# ProPrj_T113__2026-08-06.net
KiCad netlist of a schematic drawn in EasyEDA Pro
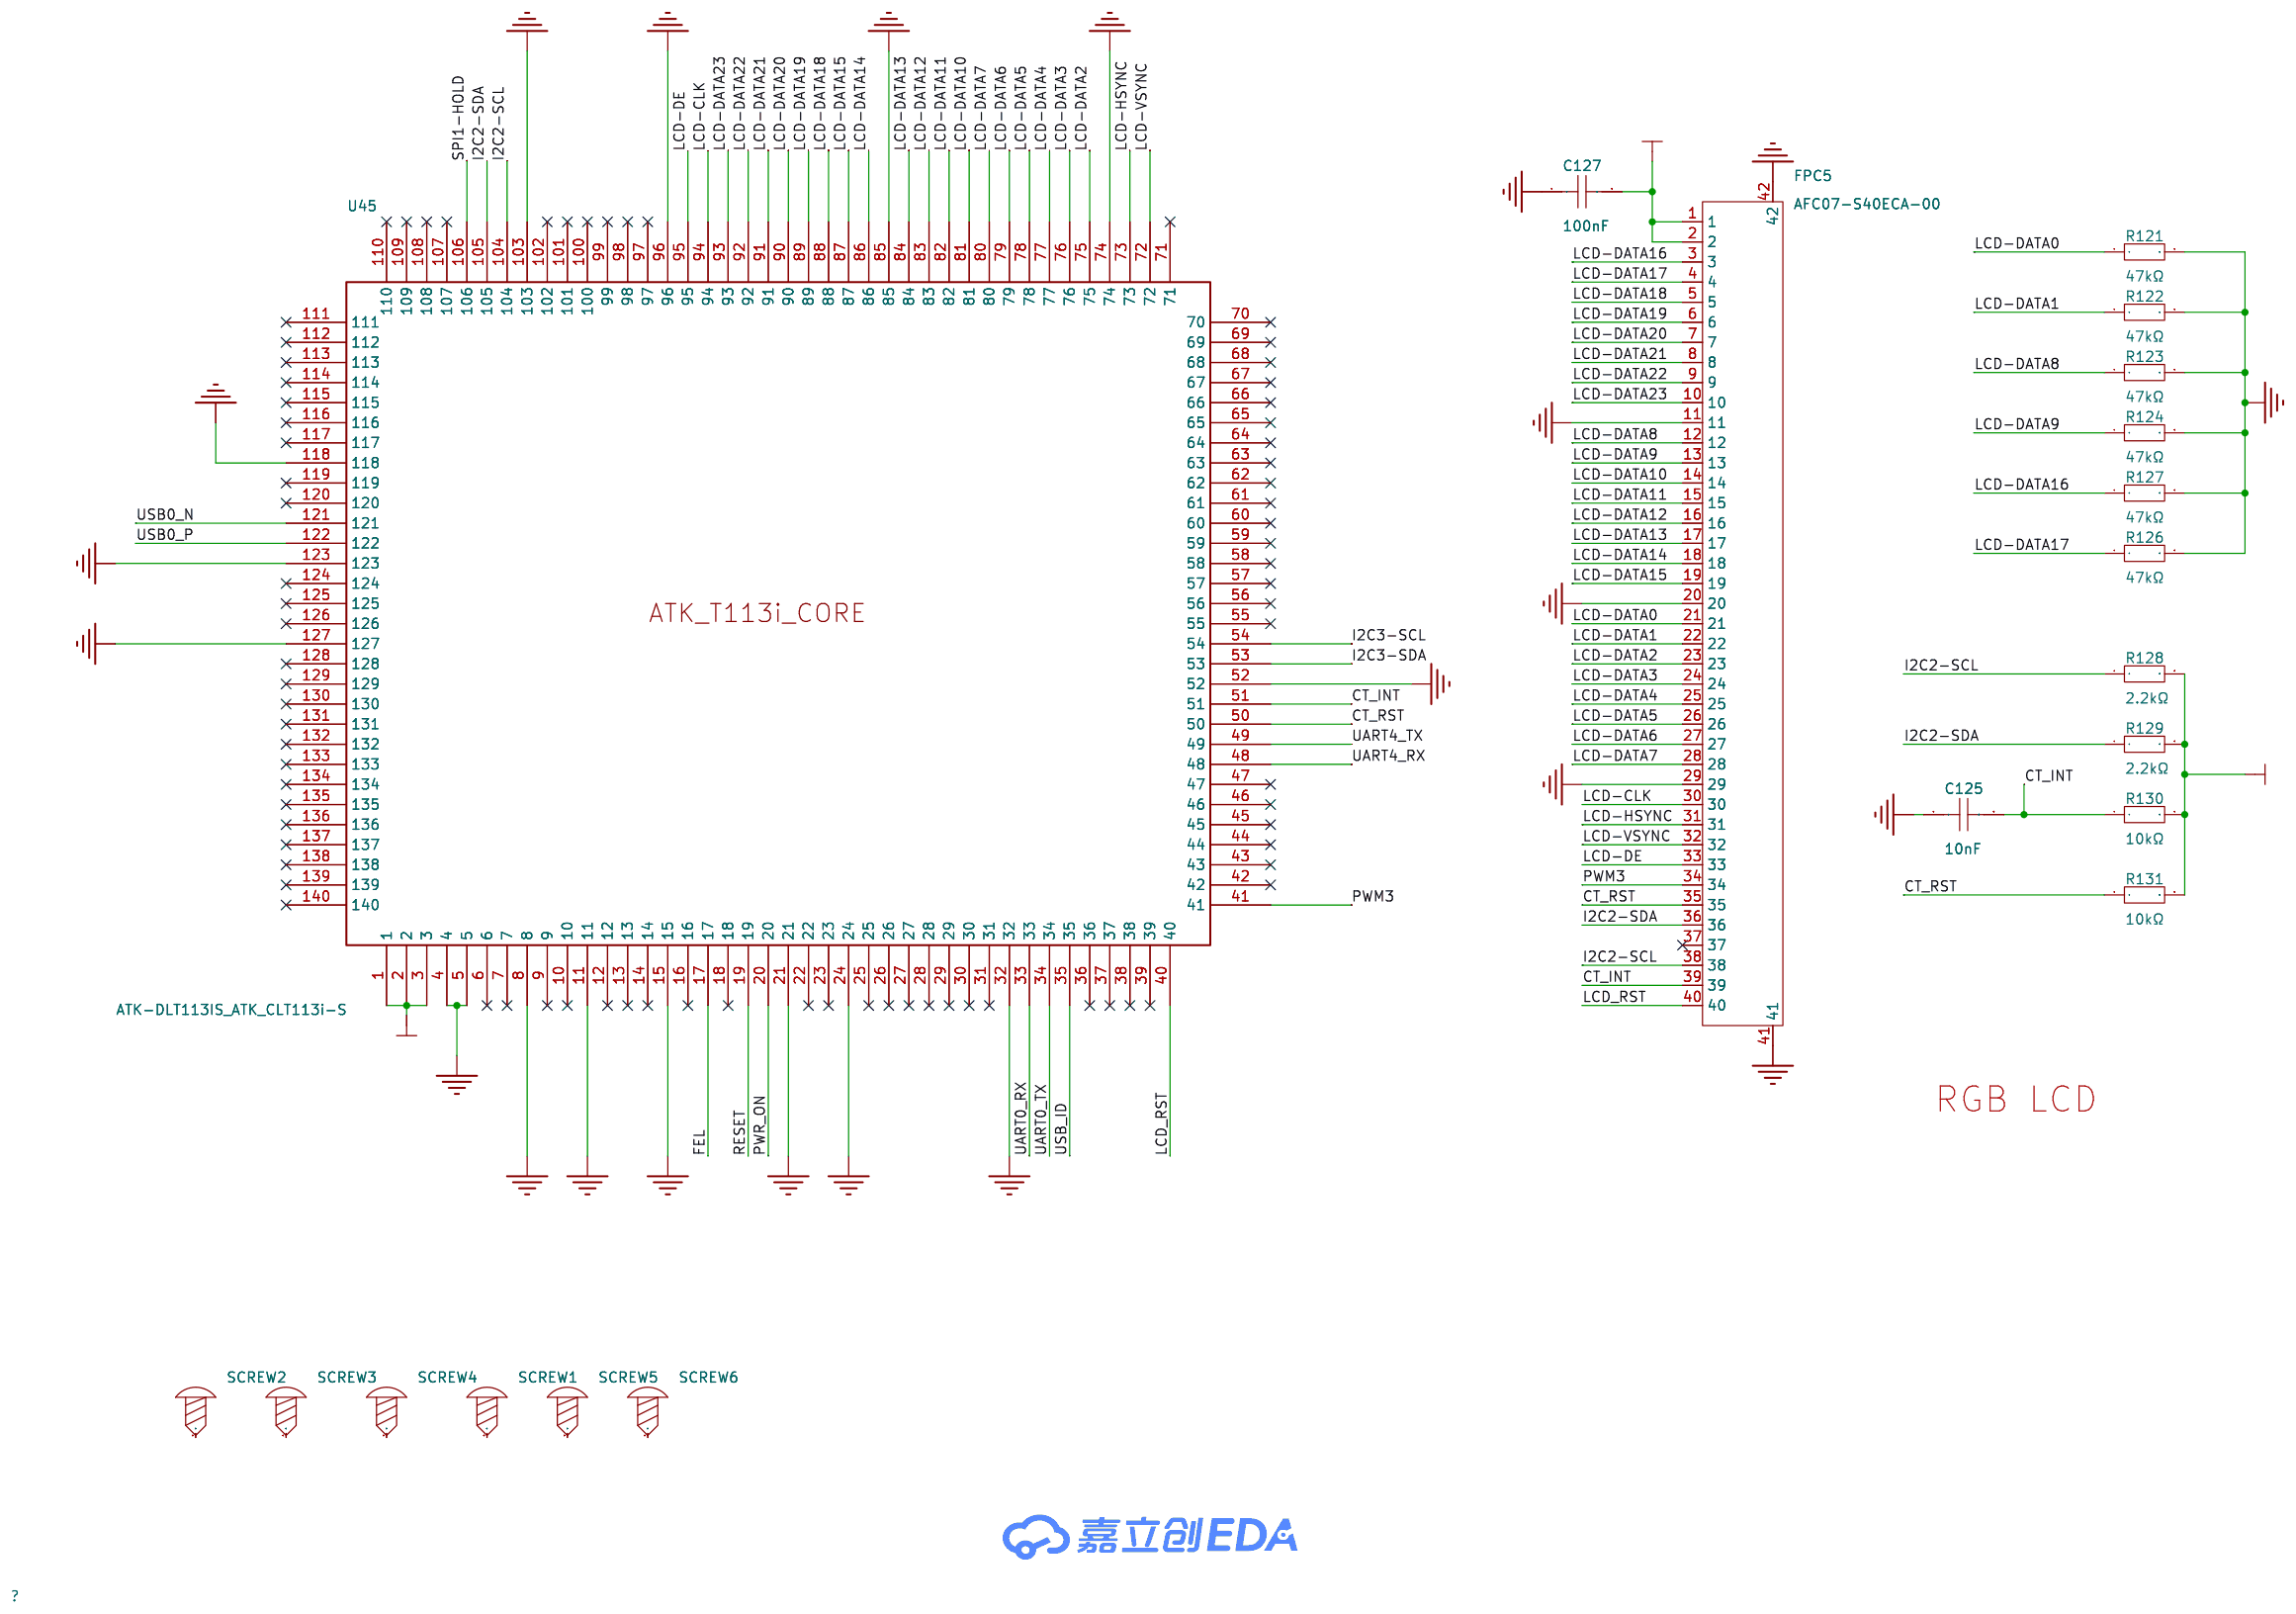
[diagram p0: P1]
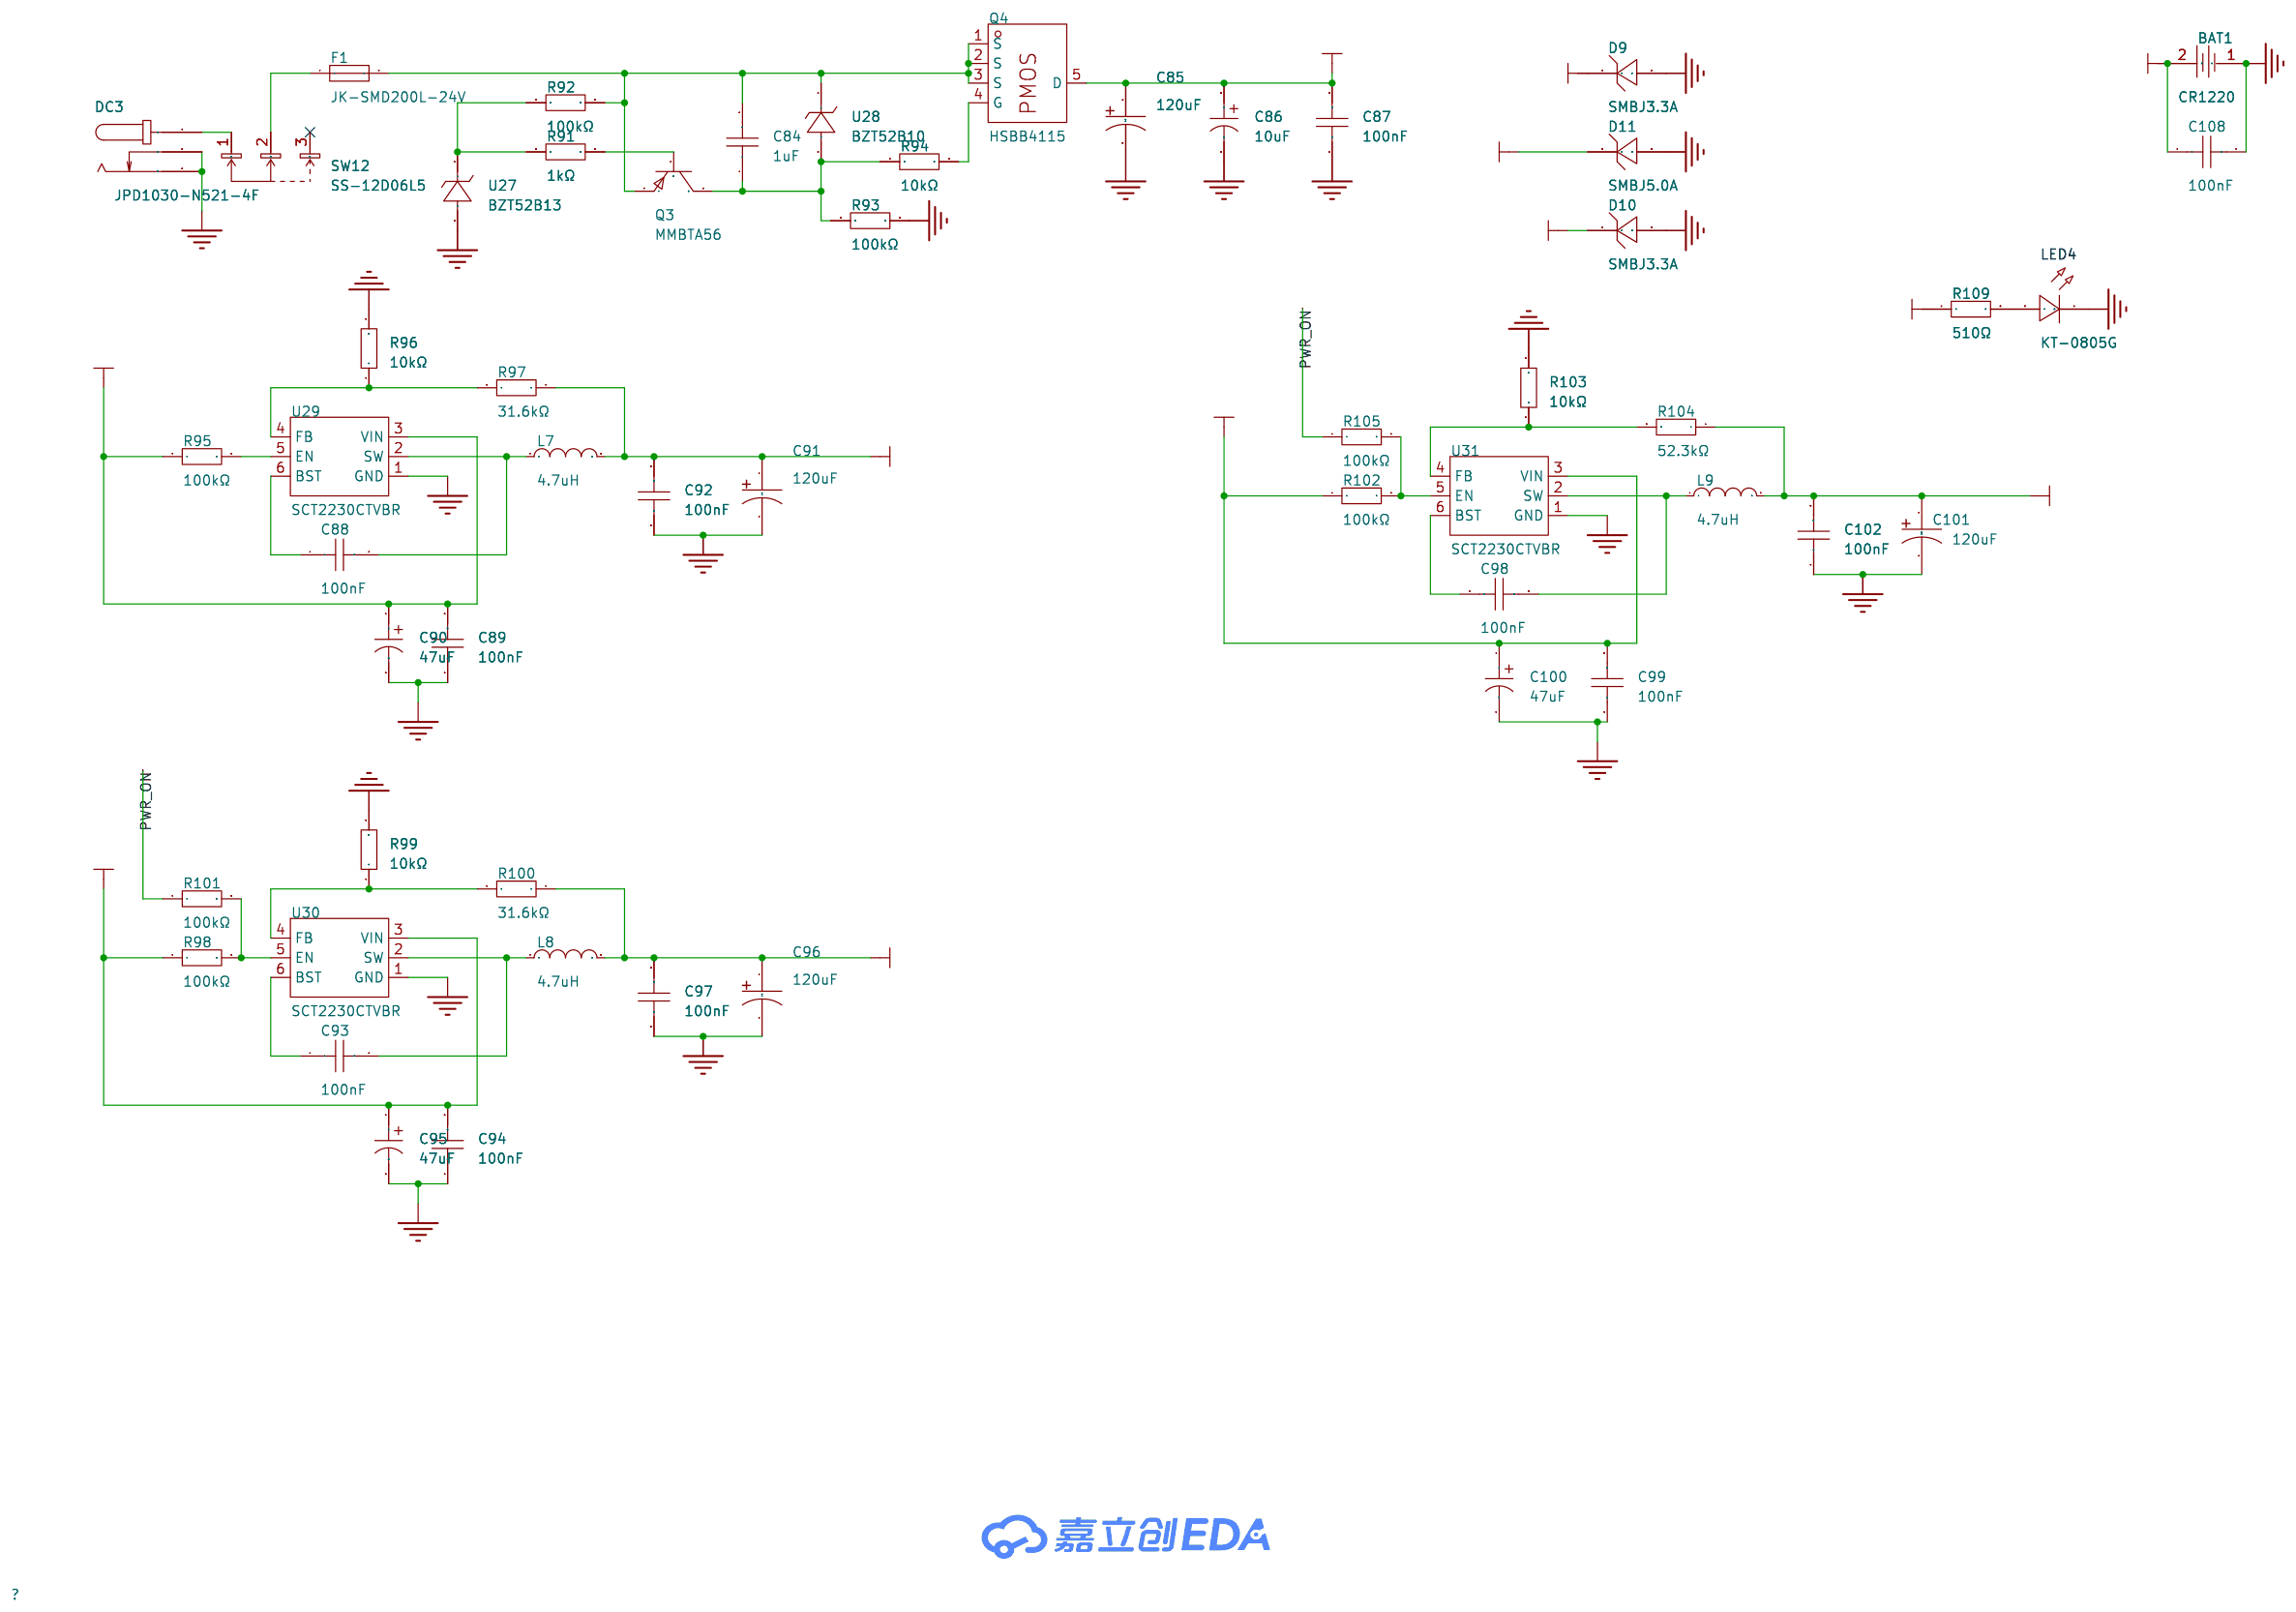
[diagram p1: P4]
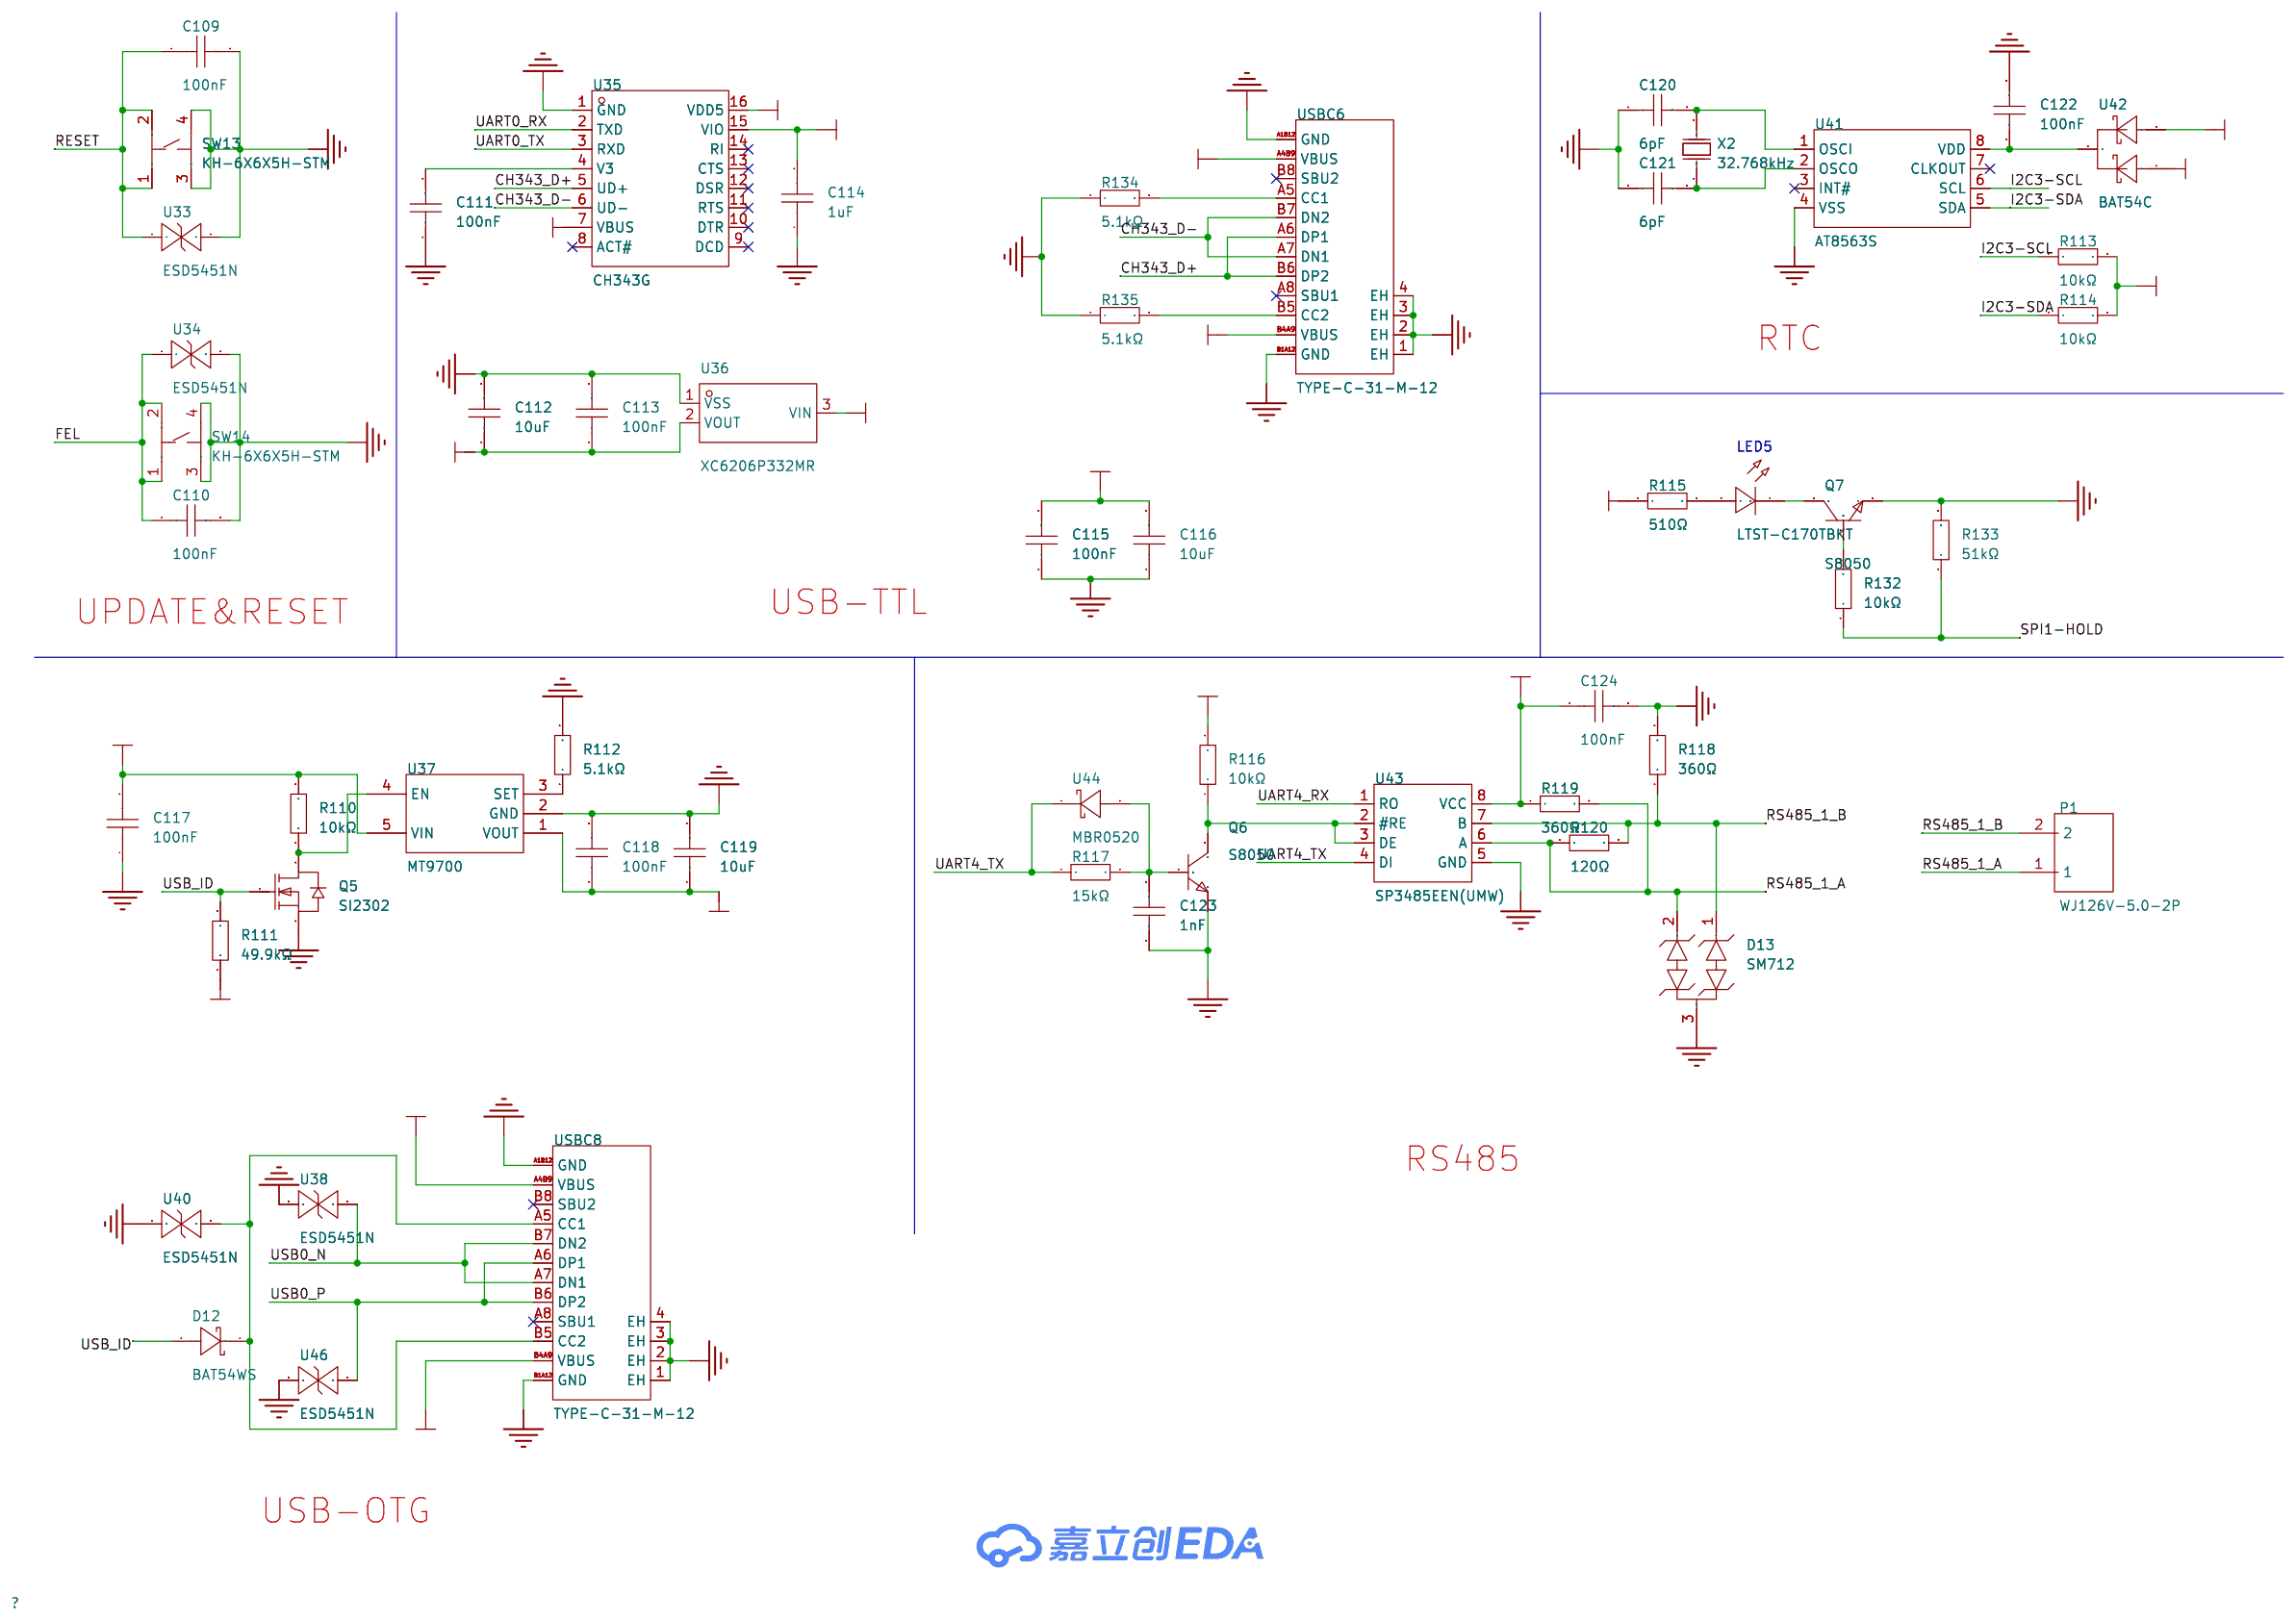
[diagram p2: P5]

(export (version "E")
  (design (tool "Eeschema 10.0.6"))
  (components
    (comp (ref "C125")
      (value "10nF")
      (footprint "easyedapro:C0805")
      (fields
        (field (name "Manufacturer Part") "CL21B103KBANNNC")
        (field (name "Manufacturer") "SAMSUNG(三星)")
      )
      (libsource (lib "easyedapro") (part "CapAcitance"))
    )
    (comp (ref "C127")
      (value "100nF")
      (footprint "easyedapro:C0805")
      (description "容值:100nF;精度:±10%;额定电压:50V;温度系数:X7R;")
      (fields
        (field (name "Manufacturer Part") "CC0805KRX7R9BB104")
        (field (name "Manufacturer") "YAGEO(国巨)")
      )
      (libsource (lib "easyedapro") (part "CapAcitance"))
    )
    (comp (ref "FPC5")
      (value "AFC07-S40ECA-00")
      (footprint "easyedapro:FPC-SMD_P0.50-40P_LCS-SJ-H2.0")
      (description "锁定特性:抽屉式;触点类型:上接;触点数量:40P;间距:0.5mm;安装方式:卧贴;")
      (fields (field (name "Manufacturer") "JS(钜硕电子)"))
      (libsource (lib "easyedapro") (part "AFC07-S40ECA-00"))
    )
    (comp (ref "R121")
      (value "47kΩ")
      (footprint "easyedapro:R0805")
      (fields
        (field (name "Manufacturer Part") "0805W8F4702T5E")
        (field (name "Manufacturer") "UNI-ROYAL(厚声)")
      )
      (libsource (lib "easyedapro") (part "电阻"))
    )
    (comp (ref "R122")
      (value "47kΩ")
      (footprint "easyedapro:R0805")
      (fields
        (field (name "Manufacturer Part") "0805W8F4702T5E")
        (field (name "Manufacturer") "UNI-ROYAL(厚声)")
      )
      (libsource (lib "easyedapro") (part "电阻"))
    )
    (comp (ref "R123")
      (value "47kΩ")
      (footprint "easyedapro:R0805")
      (fields
        (field (name "Manufacturer Part") "0805W8F4702T5E")
        (field (name "Manufacturer") "UNI-ROYAL(厚声)")
      )
      (libsource (lib "easyedapro") (part "电阻"))
    )
    (comp (ref "R124")
      (value "47kΩ")
      (footprint "easyedapro:R0805")
      (fields
        (field (name "Manufacturer Part") "0805W8F4702T5E")
        (field (name "Manufacturer") "UNI-ROYAL(厚声)")
      )
      (libsource (lib "easyedapro") (part "电阻"))
    )
    (comp (ref "R126")
      (value "47kΩ")
      (footprint "easyedapro:R0805")
      (fields
        (field (name "Manufacturer Part") "0805W8F4702T5E")
        (field (name "Manufacturer") "UNI-ROYAL(厚声)")
      )
      (libsource (lib "easyedapro") (part "电阻"))
    )
    (comp (ref "R127")
      (value "47kΩ")
      (footprint "easyedapro:R0805")
      (fields
        (field (name "Manufacturer Part") "0805W8F4702T5E")
        (field (name "Manufacturer") "UNI-ROYAL(厚声)")
      )
      (libsource (lib "easyedapro") (part "电阻"))
    )
    (comp (ref "R128")
      (value "2.2kΩ")
      (footprint "easyedapro:R0805")
      (fields
        (field (name "Manufacturer Part") "0805W8F2201T5E")
        (field (name "Manufacturer") "UNI-ROYAL(厚声)")
      )
      (libsource (lib "easyedapro") (part "电阻"))
    )
    (comp (ref "R129")
      (value "2.2kΩ")
      (footprint "easyedapro:R0805")
      (fields
        (field (name "Manufacturer Part") "0805W8F2201T5E")
        (field (name "Manufacturer") "UNI-ROYAL(厚声)")
      )
      (libsource (lib "easyedapro") (part "电阻"))
    )
    (comp (ref "R130")
      (value "10kΩ")
      (footprint "easyedapro:R0805")
      (fields
        (field (name "Manufacturer Part") "0805W8F1002T5E")
        (field (name "Manufacturer") "UNI-ROYAL(厚声)")
      )
      (libsource (lib "easyedapro") (part "电阻"))
    )
    (comp (ref "R131")
      (value "10kΩ")
      (footprint "easyedapro:R0805")
      (fields
        (field (name "Manufacturer Part") "0805W8F1002T5E")
        (field (name "Manufacturer") "UNI-ROYAL(厚声)")
      )
      (libsource (lib "easyedapro") (part "电阻"))
    )
    (comp (ref "SCREW1")
      (value "~")
      (footprint "easyedapro:M3螺丝")
      (libsource (lib "easyedapro") (part "螺丝孔"))
    )
    (comp (ref "SCREW2")
      (value "~")
      (footprint "easyedapro:M3螺丝")
      (libsource (lib "easyedapro") (part "螺丝孔"))
    )
    (comp (ref "SCREW3")
      (value "~")
      (footprint "easyedapro:M3螺丝")
      (libsource (lib "easyedapro") (part "螺丝孔"))
    )
    (comp (ref "SCREW4")
      (value "~")
      (footprint "easyedapro:M3螺丝")
      (libsource (lib "easyedapro") (part "螺丝孔"))
    )
    (comp (ref "SCREW5")
      (value "~")
      (footprint "easyedapro:M3螺丝")
      (libsource (lib "easyedapro") (part "螺丝孔"))
    )
    (comp (ref "SCREW6")
      (value "~")
      (footprint "easyedapro:M3螺丝")
      (libsource (lib "easyedapro") (part "螺丝孔"))
    )
    (comp (ref "U45")
      (value "ATK_CLT113i-S")
      (footprint "easyedapro:ATK-DLT113IS:ATK_CLT113i_CORE")
      (libsource (lib "easyedapro") (part "ATK-DLT113IS_ATK_CLT113i-S"))
    )
    (comp (ref "BAT1")
      (value "CR1220")
      (footprint "easyedapro:TH_BD12.5-P12.0-RD-CR1220")
      (description "CR1220 卧式插脚一体式钮扣电池 直接插件安装 DIP 连接器类型：电池+焊脚一体式 电池规格：CR1220 电压：3V 容量：40mAH 直径：12.5MM 厚度：2MM")
      (fields (field (name "Manufacturer") "LX(连欣科技)"))
      (libsource (lib "easyedapro") (part "CR1220"))
    )
    (comp (ref "C84")
      (value "1uF")
      (footprint "easyedapro:C0805")
      (description "容值:1uF;精度:±10%;额定电压:50V;温度系数:X7R;")
      (fields
        (field (name "Manufacturer Part") "CL21B105KBFNNNE")
        (field (name "Manufacturer") "SAMSUNG(三星)")
      )
      (libsource (lib "easyedapro") (part "CapAcitance"))
    )
    (comp (ref "C85")
      (value "120uF")
      (footprint "easyedapro:CAP-SMD_BD6.3-L6.6-W6.6-FD")
      (description "容值:120uF;精度:±20%;额定电压:20V;纹波电流:160mA@120Hz;等效串联电阻:25mΩ;类型:聚合物;")
      (fields (field (name "Manufacturer Part") "20SVPF120M") (field (name "Manufacturer") "PANASONIC(松下)"))
      (libsource (lib "easyedapro") (part "20SVPF120M"))
    )
    (comp (ref "C86")
      (value "10uF")
      (footprint "easyedapro:CAP-SMD_BD4.0-L4.3-W4.3-LS5.0-FD")
      (description "容值:10uF;精度:±20%;额定电压:25V;纹波电流:15mA@120Hz;等效串联电阻(ESR):-;")
      (fields
        (field (name "Manufacturer Part") "RVT1E100M0405 10UF 25V")
        (field (name "Manufacturer") "DMBJ(振宝佳)")
      )
      (libsource (lib "easyedapro") (part "RVT1E100M0405 10UF 25V"))
    )
    (comp (ref "C87")
      (value "100nF")
      (footprint "easyedapro:C0805")
      (description "容值:100nF;精度:±10%;额定电压:50V;温度系数:X7R;")
      (fields
        (field (name "Manufacturer Part") "CC0805KRX7R9BB104")
        (field (name "Manufacturer") "YAGEO(国巨)")
      )
      (libsource (lib "easyedapro") (part "CapAcitance"))
    )
    (comp (ref "C88")
      (value "100nF")
      (footprint "easyedapro:C0805")
      (description "容值:100nF;精度:±10%;额定电压:50V;温度系数:X7R;")
      (fields
        (field (name "Manufacturer Part") "CC0805KRX7R9BB104")
        (field (name "Manufacturer") "YAGEO(国巨)")
      )
      (libsource (lib "easyedapro") (part "CapAcitance"))
    )
    (comp (ref "C89")
      (value "100nF")
      (footprint "easyedapro:C0805")
      (description "容值:100nF;精度:±10%;额定电压:50V;温度系数:X7R;")
      (fields
        (field (name "Manufacturer Part") "CC0805KRX7R9BB104")
        (field (name "Manufacturer") "YAGEO(国巨)")
      )
      (libsource (lib "easyedapro") (part "CapAcitance"))
    )
    (comp (ref "C90")
      (value "47uF")
      (footprint "easyedapro:CAP-SMD_BD6.3-L6.6-W6.6-LS7.2-FD")
      (description "容值:47uF;精度:±20%;额定电压:25V;纹波电流:49mA@120Hz;等效串联电阻(ESR):-;")
      (fields
        (field (name "Manufacturer Part") "RVT1E470M0605 47UF 25V")
        (field (name "Manufacturer") "DMBJ(振宝佳)")
      )
      (libsource (lib "easyedapro") (part "RVT1E470M0605 47UF 25V"))
    )
    (comp (ref "C91")
      (value "120uF")
      (footprint "easyedapro:CAP-SMD_BD6.3-L6.6-W6.6-FD")
      (description "容值:120uF;精度:±20%;额定电压:20V;纹波电流:160mA@120Hz;等效串联电阻:25mΩ;类型:聚合物;")
      (fields (field (name "Manufacturer Part") "20SVPF120M") (field (name "Manufacturer") "PANASONIC(松下)"))
      (libsource (lib "easyedapro") (part "20SVPF120M"))
    )
    (comp (ref "C92")
      (value "100nF")
      (footprint "easyedapro:C0805")
      (description "容值:100nF;精度:±10%;额定电压:50V;温度系数:X7R;")
      (fields
        (field (name "Manufacturer Part") "CC0805KRX7R9BB104")
        (field (name "Manufacturer") "YAGEO(国巨)")
      )
      (libsource (lib "easyedapro") (part "CapAcitance"))
    )
    (comp (ref "C93")
      (value "100nF")
      (footprint "easyedapro:C0805")
      (description "容值:100nF;精度:±10%;额定电压:50V;温度系数:X7R;")
      (fields
        (field (name "Manufacturer Part") "CC0805KRX7R9BB104")
        (field (name "Manufacturer") "YAGEO(国巨)")
      )
      (libsource (lib "easyedapro") (part "CapAcitance"))
    )
    (comp (ref "C94")
      (value "100nF")
      (footprint "easyedapro:C0805")
      (description "容值:100nF;精度:±10%;额定电压:50V;温度系数:X7R;")
      (fields
        (field (name "Manufacturer Part") "CC0805KRX7R9BB104")
        (field (name "Manufacturer") "YAGEO(国巨)")
      )
      (libsource (lib "easyedapro") (part "CapAcitance"))
    )
    (comp (ref "C95")
      (value "47uF")
      (footprint "easyedapro:CAP-SMD_BD6.3-L6.6-W6.6-LS7.2-FD")
      (description "容值:47uF;精度:±20%;额定电压:25V;纹波电流:49mA@120Hz;等效串联电阻(ESR):-;")
      (fields
        (field (name "Manufacturer Part") "RVT1E470M0605 47UF 25V")
        (field (name "Manufacturer") "DMBJ(振宝佳)")
      )
      (libsource (lib "easyedapro") (part "RVT1E470M0605 47UF 25V"))
    )
    (comp (ref "C96")
      (value "120uF")
      (footprint "easyedapro:CAP-SMD_BD6.3-L6.6-W6.6-FD")
      (description "容值:120uF;精度:±20%;额定电压:20V;纹波电流:160mA@120Hz;等效串联电阻:25mΩ;类型:聚合物;")
      (fields (field (name "Manufacturer Part") "20SVPF120M") (field (name "Manufacturer") "PANASONIC(松下)"))
      (libsource (lib "easyedapro") (part "20SVPF120M"))
    )
    (comp (ref "C97")
      (value "100nF")
      (footprint "easyedapro:C0805")
      (description "容值:100nF;精度:±10%;额定电压:50V;温度系数:X7R;")
      (fields
        (field (name "Manufacturer Part") "CC0805KRX7R9BB104")
        (field (name "Manufacturer") "YAGEO(国巨)")
      )
      (libsource (lib "easyedapro") (part "CapAcitance"))
    )
    (comp (ref "C98")
      (value "100nF")
      (footprint "easyedapro:C0805")
      (description "容值:100nF;精度:±10%;额定电压:50V;温度系数:X7R;")
      (fields
        (field (name "Manufacturer Part") "CC0805KRX7R9BB104")
        (field (name "Manufacturer") "YAGEO(国巨)")
      )
      (libsource (lib "easyedapro") (part "CapAcitance"))
    )
    (comp (ref "C99")
      (value "100nF")
      (footprint "easyedapro:C0805")
      (description "容值:100nF;精度:±10%;额定电压:50V;温度系数:X7R;")
      (fields
        (field (name "Manufacturer Part") "CC0805KRX7R9BB104")
        (field (name "Manufacturer") "YAGEO(国巨)")
      )
      (libsource (lib "easyedapro") (part "CapAcitance"))
    )
    (comp (ref "C100")
      (value "47uF")
      (footprint "easyedapro:CAP-SMD_BD6.3-L6.6-W6.6-LS7.2-FD")
      (description "容值:47uF;精度:±20%;额定电压:25V;纹波电流:49mA@120Hz;等效串联电阻(ESR):-;")
      (fields
        (field (name "Manufacturer Part") "RVT1E470M0605 47UF 25V")
        (field (name "Manufacturer") "DMBJ(振宝佳)")
      )
      (libsource (lib "easyedapro") (part "RVT1E470M0605 47UF 25V"))
    )
    (comp (ref "C101")
      (value "120uF")
      (footprint "easyedapro:CAP-SMD_BD6.3-L6.6-W6.6-FD")
      (description "容值:120uF;精度:±20%;额定电压:20V;纹波电流:160mA@120Hz;等效串联电阻:25mΩ;类型:聚合物;")
      (fields (field (name "Manufacturer Part") "20SVPF120M") (field (name "Manufacturer") "PANASONIC(松下)"))
      (libsource (lib "easyedapro") (part "20SVPF120M"))
    )
    (comp (ref "C102")
      (value "100nF")
      (footprint "easyedapro:C0805")
      (description "容值:100nF;精度:±10%;额定电压:50V;温度系数:X7R;")
      (fields
        (field (name "Manufacturer Part") "CC0805KRX7R9BB104")
        (field (name "Manufacturer") "YAGEO(国巨)")
      )
      (libsource (lib "easyedapro") (part "CapAcitance"))
    )
    (comp (ref "C108")
      (value "100nF")
      (footprint "easyedapro:C0805")
      (description "容值:100nF;精度:±10%;额定电压:50V;温度系数:X7R;")
      (fields
        (field (name "Manufacturer Part") "CC0805KRX7R9BB104")
        (field (name "Manufacturer") "YAGEO(国巨)")
      )
      (libsource (lib "easyedapro") (part "CapAcitance"))
    )
    (comp (ref "D9")
      (value "SMBJ3.3A")
      (footprint "easyedapro:SMB_L4.6-W3.6-LS5.3-RD")
      (description "极性:单向;反向截止电压(Vrwm):3.3V;钳位电压:8V;峰值脉冲电流(Ipp):75A@10/1000us;峰值脉冲功率(Ppp):600W@10/1000us;击穿电压:6.5V;")
      (fields (field (name "Manufacturer") "R+O(宏嘉诚)"))
      (libsource (lib "easyedapro") (part "SMBJ3.3A_C19077556"))
    )
    (comp (ref "D10")
      (value "SMBJ3.3A")
      (footprint "easyedapro:SMB_L4.6-W3.6-LS5.3-RD")
      (description "极性:单向;反向截止电压(Vrwm):3.3V;钳位电压:8V;峰值脉冲电流(Ipp):75A@10/1000us;峰值脉冲功率(Ppp):600W@10/1000us;击穿电压:6.5V;")
      (fields (field (name "Manufacturer") "R+O(宏嘉诚)"))
      (libsource (lib "easyedapro") (part "SMBJ3.3A_C19077556"))
    )
    (comp (ref "D11")
      (value "SMBJ5.0A")
      (footprint "easyedapro:SMB_L4.6-W3.6-LS5.3-RD")
      (description "反向截止电压(Vrwm):5V;钳位电压:9.2V;峰值脉冲电流(Ipp):65.3A;峰值脉冲功率(Ppp):600W;击穿电压:6.4V;")
      (fields (field (name "Manufacturer") "Littelfuse(美国力特)"))
      (libsource (lib "easyedapro") (part "SMBJ5.0A_C83333"))
    )
    (comp (ref "DC3")
      (value "JPD1030-N521-4F")
      (footprint "easyedapro:DC-IN-TH_JPD1030-N521-4F")
      (description "连接器类型:DC电源插座;安装方式:弯插;触点内径:-;触点外径:-;额定电流:5A;额定电压:20V;工作温度范围:-25°C~+70°C;")
      (fields (field (name "Manufacturer") "FOXCONN(富士康)"))
      (libsource (lib "easyedapro") (part "JPD1030-N521-4F"))
    )
    (comp (ref "F1")
      (value "JK-SMD200L-24V")
      (footprint "easyedapro:F2920")
      (description "耐压(Vmax):24V;最大电流(Imax):100A;保持电流(Ihold):2A;跳闸电流(Itrip):4A;")
      (fields (field (name "Manufacturer") "JK(金科)"))
      (libsource (lib "easyedapro") (part "JK-SMD200L-24V"))
    )
    (comp (ref "L7")
      (value "4.7uH")
      (footprint "easyedapro:IND-SMD_L4.6-W4.1-A")
      (description "电感值:4.7uH;精度:±20%;额定电流:3A;饱和电流(Isat):3.5A;类型:一体成型电感;")
      (fields (field (name "Manufacturer Part") "SRG0420-4R7-M") (field (name "Manufacturer") "JIERR(捷而瑞)"))
      (libsource (lib "easyedapro") (part "SRG0420-4R7-M"))
    )
    (comp (ref "L8")
      (value "4.7uH")
      (footprint "easyedapro:IND-SMD_L4.6-W4.1-A")
      (description "电感值:4.7uH;精度:±20%;额定电流:3A;饱和电流(Isat):3.5A;类型:一体成型电感;")
      (fields (field (name "Manufacturer Part") "SRG0420-4R7-M") (field (name "Manufacturer") "JIERR(捷而瑞)"))
      (libsource (lib "easyedapro") (part "SRG0420-4R7-M"))
    )
    (comp (ref "L9")
      (value "4.7uH")
      (footprint "easyedapro:IND-SMD_L4.6-W4.1-A")
      (description "电感值:4.7uH;精度:±20%;额定电流:3A;饱和电流(Isat):3.5A;类型:一体成型电感;")
      (fields (field (name "Manufacturer Part") "SRG0420-4R7-M") (field (name "Manufacturer") "JIERR(捷而瑞)"))
      (libsource (lib "easyedapro") (part "SRG0420-4R7-M"))
    )
    (comp (ref "LED4")
      (value "KT-0805G")
      (footprint "easyedapro:LED_0805")
      (fields (field (name "Manufacturer") "KENTO"))
      (libsource (lib "easyedapro") (part "LED_G"))
    )
    (comp (ref "Q3")
      (value "MMBTA56")
      (footprint "easyedapro:SOT-23-3_L2.9-W1.3-P1.90-LS2.4-BL-1")
      (description "晶体管类型:PNP;集电极电流(Ic):500mA;集射极击穿电压(Vceo):80V;耗散功率(Pd):225mW;直流电流增益(hFE):100;")
      (fields (field (name "Manufacturer") "R+O(宏嘉诚)"))
      (libsource (lib "easyedapro") (part "MMBTA56_C20069147"))
    )
    (comp (ref "Q4")
      (value "HSBB4115")
      (footprint "easyedapro:DFN-8_L3.0-W3.0-P0.65-BL-1")
      (fields (field (name "Manufacturer") "HUASHUO(华朔)"))
      (libsource (lib "easyedapro") (part "HSBB4115"))
    )
    (comp (ref "R91")
      (value "1kΩ")
      (footprint "easyedapro:R0805")
      (fields
        (field (name "Manufacturer Part") "0805W8F1001T5E")
        (field (name "Manufacturer") "UNI-ROYAL(厚声)")
      )
      (libsource (lib "easyedapro") (part "电阻"))
    )
    (comp (ref "R92")
      (value "100kΩ")
      (footprint "easyedapro:R0805")
      (fields
        (field (name "Manufacturer Part") "0805W8F1003T5E")
        (field (name "Manufacturer") "UNI-ROYAL(厚声)")
      )
      (libsource (lib "easyedapro") (part "电阻"))
    )
    (comp (ref "R93")
      (value "100kΩ")
      (footprint "easyedapro:R0805")
      (fields
        (field (name "Manufacturer Part") "0805W8F1003T5E")
        (field (name "Manufacturer") "UNI-ROYAL(厚声)")
      )
      (libsource (lib "easyedapro") (part "电阻"))
    )
    (comp (ref "R94")
      (value "10kΩ")
      (footprint "easyedapro:R0805")
      (fields
        (field (name "Manufacturer Part") "0805W8F1002T5E")
        (field (name "Manufacturer") "UNI-ROYAL(厚声)")
      )
      (libsource (lib "easyedapro") (part "电阻"))
    )
    (comp (ref "R95")
      (value "100kΩ")
      (footprint "easyedapro:R0805")
      (fields
        (field (name "Manufacturer Part") "0805W8F1003T5E")
        (field (name "Manufacturer") "UNI-ROYAL(厚声)")
      )
      (libsource (lib "easyedapro") (part "电阻"))
    )
    (comp (ref "R96")
      (value "10kΩ")
      (footprint "easyedapro:R0805")
      (fields
        (field (name "Manufacturer Part") "0805W8F1002T5E")
        (field (name "Manufacturer") "UNI-ROYAL(厚声)")
      )
      (libsource (lib "easyedapro") (part "电阻"))
    )
    (comp (ref "R97")
      (value "31.6kΩ")
      (footprint "easyedapro:R0805")
      (fields (field (name "Manufacturer Part") "FRC0805F3162TS") (field (name "Manufacturer") "FOJAN(富捷)"))
      (libsource (lib "easyedapro") (part "电阻"))
    )
    (comp (ref "R98")
      (value "100kΩ")
      (footprint "easyedapro:R0805")
      (fields
        (field (name "Manufacturer Part") "0805W8F1003T5E")
        (field (name "Manufacturer") "UNI-ROYAL(厚声)")
      )
      (libsource (lib "easyedapro") (part "电阻"))
    )
    (comp (ref "R99")
      (value "10kΩ")
      (footprint "easyedapro:R0805")
      (fields
        (field (name "Manufacturer Part") "0805W8F1002T5E")
        (field (name "Manufacturer") "UNI-ROYAL(厚声)")
      )
      (libsource (lib "easyedapro") (part "电阻"))
    )
    (comp (ref "R100")
      (value "31.6kΩ")
      (footprint "easyedapro:R0805")
      (fields (field (name "Manufacturer Part") "FRC0805F3162TS") (field (name "Manufacturer") "FOJAN(富捷)"))
      (libsource (lib "easyedapro") (part "电阻"))
    )
    (comp (ref "R101")
      (value "100kΩ")
      (footprint "easyedapro:R0805")
      (fields
        (field (name "Manufacturer Part") "0805W8F1003T5E")
        (field (name "Manufacturer") "UNI-ROYAL(厚声)")
      )
      (libsource (lib "easyedapro") (part "电阻"))
    )
    (comp (ref "R102")
      (value "100kΩ")
      (footprint "easyedapro:R0805")
      (fields
        (field (name "Manufacturer Part") "0805W8F1003T5E")
        (field (name "Manufacturer") "UNI-ROYAL(厚声)")
      )
      (libsource (lib "easyedapro") (part "电阻"))
    )
    (comp (ref "R103")
      (value "10kΩ")
      (footprint "easyedapro:R0805")
      (fields
        (field (name "Manufacturer Part") "0805W8F1002T5E")
        (field (name "Manufacturer") "UNI-ROYAL(厚声)")
      )
      (libsource (lib "easyedapro") (part "电阻"))
    )
    (comp (ref "R104")
      (value "52.3kΩ")
      (footprint "easyedapro:R0805")
      (fields (field (name "Manufacturer Part") "ARG05BTC5232") (field (name "Manufacturer") "Viking(光颉)"))
      (libsource (lib "easyedapro") (part "电阻"))
    )
    (comp (ref "R105")
      (value "100kΩ")
      (footprint "easyedapro:R0805")
      (fields
        (field (name "Manufacturer Part") "0805W8F1003T5E")
        (field (name "Manufacturer") "UNI-ROYAL(厚声)")
      )
      (libsource (lib "easyedapro") (part "电阻"))
    )
    (comp (ref "R109")
      (value "510Ω")
      (footprint "easyedapro:R0805")
      (description "电阻类型:厚膜电阻;阻值:510Ω;精度:±1%;功率:125mW;工作电压:150V;温度系数:±100ppm/℃;")
      (fields
        (field (name "Manufacturer Part") "0805W8F5100T5E")
        (field (name "Manufacturer") "UNI-ROYAL(厚声)")
      )
      (libsource (lib "easyedapro") (part "电阻"))
    )
    (comp (ref "SW12")
      (value "SS-12D06L5")
      (footprint "easyedapro:SW-TH_3P-P4.70_L11.1-W12.7")
      (description "电路结构:单刀双掷;安装方式:-;开关颜色:黑色;额定电流:3A;额定电压:125V;工作寿命:1万次;")
      (fields (field (name "Manufacturer") "XKB Connection(中国星坤)"))
      (libsource (lib "easyedapro") (part "SS-12D06L5"))
    )
    (comp (ref "U27")
      (value "BZT52B13")
      (footprint "easyedapro:SOD-123_L2.7-W1.6-LS3.7-RD")
      (description "二极管配置:独立式;稳压值(标称值):13V;稳压值(范围):12.74V~13.26V;耗散功率(Pd):500mW;")
      (fields (field (name "Manufacturer") "R+O(宏嘉诚)"))
      (libsource (lib "easyedapro") (part "BZT52B13_C22399883"))
    )
    (comp (ref "U28")
      (value "BZT52B10")
      (footprint "easyedapro:SOD-123_L2.7-W1.6-LS3.7-RD")
      (description "二极管配置:独立式;稳压值(标称值):10V;稳压值(范围):9.8V~10.2V;耗散功率(Pd):500mW;")
      (fields (field (name "Manufacturer") "R+O(宏嘉诚)"))
      (libsource (lib "easyedapro") (part "BZT52B10_C22395568"))
    )
    (comp (ref "U29")
      (value "SCT2230CTVBR")
      (footprint "easyedapro:TSOT-23-6_L2.9-W1.6-P0.95-LS2.8-BL")
      (description "功能类型:降压型;输出类型:可调;工作电压:4.2V~17V;输出电压:800mV~7V;输出电流:3A;")
      (fields (field (name "Manufacturer") "SCT(芯洲科技)"))
      (libsource (lib "easyedapro") (part "SCT2230CTVBR"))
    )
    (comp (ref "U30")
      (value "SCT2230CTVBR")
      (footprint "easyedapro:TSOT-23-6_L2.9-W1.6-P0.95-LS2.8-BL")
      (description "功能类型:降压型;输出类型:可调;工作电压:4.2V~17V;输出电压:800mV~7V;输出电流:3A;")
      (fields (field (name "Manufacturer") "SCT(芯洲科技)"))
      (libsource (lib "easyedapro") (part "SCT2230CTVBR"))
    )
    (comp (ref "U31")
      (value "SCT2230CTVBR")
      (footprint "easyedapro:TSOT-23-6_L2.9-W1.6-P0.95-LS2.8-BL")
      (description "功能类型:降压型;输出类型:可调;工作电压:4.2V~17V;输出电压:800mV~7V;输出电流:3A;")
      (fields (field (name "Manufacturer") "SCT(芯洲科技)"))
      (libsource (lib "easyedapro") (part "SCT2230CTVBR"))
    )
    (comp (ref "C109")
      (value "100nF")
      (footprint "easyedapro:C0805")
      (description "容值:100nF;精度:±10%;额定电压:50V;温度系数:X7R;")
      (fields
        (field (name "Manufacturer Part") "CC0805KRX7R9BB104")
        (field (name "Manufacturer") "YAGEO(国巨)")
      )
      (libsource (lib "easyedapro") (part "CapAcitance"))
    )
    (comp (ref "C110")
      (value "100nF")
      (footprint "easyedapro:C0805")
      (description "容值:100nF;精度:±10%;额定电压:50V;温度系数:X7R;")
      (fields
        (field (name "Manufacturer Part") "CC0805KRX7R9BB104")
        (field (name "Manufacturer") "YAGEO(国巨)")
      )
      (libsource (lib "easyedapro") (part "CapAcitance"))
    )
    (comp (ref "C111")
      (value "100nF")
      (footprint "easyedapro:C0805")
      (description "容值:100nF;精度:±10%;额定电压:50V;温度系数:X7R;")
      (fields
        (field (name "Manufacturer Part") "CC0805KRX7R9BB104")
        (field (name "Manufacturer") "YAGEO(国巨)")
      )
      (libsource (lib "easyedapro") (part "CapAcitance"))
    )
    (comp (ref "C112")
      (value "10uF")
      (footprint "easyedapro:C0805")
      (description "容值:10uF;精度:±10%;额定电压:25V;温度系数:X5R;")
      (fields
        (field (name "Manufacturer Part") "CL21A106KAYNNNE")
        (field (name "Manufacturer") "SAMSUNG(三星)")
      )
      (libsource (lib "easyedapro") (part "CapAcitance"))
    )
    (comp (ref "C113")
      (value "100nF")
      (footprint "easyedapro:C0805")
      (description "容值:100nF;精度:±10%;额定电压:50V;温度系数:X7R;")
      (fields
        (field (name "Manufacturer Part") "CC0805KRX7R9BB104")
        (field (name "Manufacturer") "YAGEO(国巨)")
      )
      (libsource (lib "easyedapro") (part "CapAcitance"))
    )
    (comp (ref "C114")
      (value "1uF")
      (footprint "easyedapro:C0805")
      (description "容值:1uF;精度:±10%;额定电压:50V;温度系数:X7R;")
      (fields
        (field (name "Manufacturer Part") "CL21B105KBFNNNE")
        (field (name "Manufacturer") "SAMSUNG(三星)")
      )
      (libsource (lib "easyedapro") (part "CapAcitance"))
    )
    (comp (ref "C115")
      (value "100nF")
      (footprint "easyedapro:C0805")
      (description "容值:100nF;精度:±10%;额定电压:50V;温度系数:X7R;")
      (fields
        (field (name "Manufacturer Part") "CC0805KRX7R9BB104")
        (field (name "Manufacturer") "YAGEO(国巨)")
      )
      (libsource (lib "easyedapro") (part "CapAcitance"))
    )
    (comp (ref "C116")
      (value "10uF")
      (footprint "easyedapro:C0805")
      (description "容值:10uF;精度:±10%;额定电压:25V;温度系数:X5R;")
      (fields
        (field (name "Manufacturer Part") "CL21A106KAYNNNE")
        (field (name "Manufacturer") "SAMSUNG(三星)")
      )
      (libsource (lib "easyedapro") (part "CapAcitance"))
    )
    (comp (ref "C117")
      (value "100nF")
      (footprint "easyedapro:C0805")
      (description "容值:100nF;精度:±10%;额定电压:50V;温度系数:X7R;")
      (fields
        (field (name "Manufacturer Part") "CC0805KRX7R9BB104")
        (field (name "Manufacturer") "YAGEO(国巨)")
      )
      (libsource (lib "easyedapro") (part "CapAcitance"))
    )
    (comp (ref "C118")
      (value "100nF")
      (footprint "easyedapro:C0805")
      (description "容值:100nF;精度:±10%;额定电压:50V;温度系数:X7R;")
      (fields
        (field (name "Manufacturer Part") "CC0805KRX7R9BB104")
        (field (name "Manufacturer") "YAGEO(国巨)")
      )
      (libsource (lib "easyedapro") (part "CapAcitance"))
    )
    (comp (ref "C119")
      (value "10uF")
      (footprint "easyedapro:C0805")
      (description "容值:10uF;精度:±10%;额定电压:25V;温度系数:X5R;")
      (fields
        (field (name "Manufacturer Part") "CL21A106KAYNNNE")
        (field (name "Manufacturer") "SAMSUNG(三星)")
      )
      (libsource (lib "easyedapro") (part "CapAcitance"))
    )
    (comp (ref "C120")
      (value "6pF")
      (footprint "easyedapro:C0805")
      (fields (field (name "Manufacturer Part") "0805CG6R0C500NT") (field (name "Manufacturer") "FH(风华)"))
      (libsource (lib "easyedapro") (part "CapAcitance"))
    )
    (comp (ref "C121")
      (value "6pF")
      (footprint "easyedapro:C0805")
      (fields (field (name "Manufacturer Part") "0805CG6R0C500NT") (field (name "Manufacturer") "FH(风华)"))
      (libsource (lib "easyedapro") (part "CapAcitance"))
    )
    (comp (ref "C122")
      (value "100nF")
      (footprint "easyedapro:C0805")
      (description "容值:100nF;精度:±10%;额定电压:50V;温度系数:X7R;")
      (fields
        (field (name "Manufacturer Part") "CC0805KRX7R9BB104")
        (field (name "Manufacturer") "YAGEO(国巨)")
      )
      (libsource (lib "easyedapro") (part "CapAcitance"))
    )
    (comp (ref "C123")
      (value "1nF")
      (footprint "easyedapro:C0805")
      (description "容值:1nF;精度:±10%;额定电压:50V;温度系数:X7R;")
      (fields
        (field (name "Manufacturer Part") "CL21B102KBCNNNC")
        (field (name "Manufacturer") "SAMSUNG(三星)")
      )
      (libsource (lib "easyedapro") (part "CapAcitance"))
    )
    (comp (ref "C124")
      (value "100nF")
      (footprint "easyedapro:C0805")
      (description "容值:100nF;精度:±10%;额定电压:50V;温度系数:X7R;")
      (fields
        (field (name "Manufacturer Part") "CC0805KRX7R9BB104")
        (field (name "Manufacturer") "YAGEO(国巨)")
      )
      (libsource (lib "easyedapro") (part "CapAcitance"))
    )
    (comp (ref "D12")
      (value "BAT54WS")
      (footprint "easyedapro:SOD-323_L1.7-W1.3-LS2.6-RD-1")
      (description "二极管配置:独立式;正向压降(Vf):1V@100mA;直流反向耐压(Vr):30V;整流电流:200mA;")
      (fields (field (name "Manufacturer") "R+O(宏嘉诚)"))
      (libsource (lib "easyedapro") (part "BAT54WS_C7502694"))
    )
    (comp (ref "D13")
      (value "SM712")
      (footprint "easyedapro:SOT-23-3_L2.9-W1.3-P1.90-LS2.4-BR")
      (description "极性:双向;反向截止电压(Vrwm):12V；7V;钳位电压:16V；26V;峰值脉冲电流(Ipp):12A;峰值脉冲功率(Ppp):300W;击穿电压:7.5V；13.5V;")
      (fields (field (name "Manufacturer") "R+O(宏嘉诚)"))
      (libsource (lib "easyedapro") (part "SM712_C7420375"))
    )
    (comp (ref "LED5")
      (value "LTST-C170TBKT")
      (footprint "easyedapro:LED_0805")
      (fields (field (name "Manufacturer") "LITEON(光宝)"))
      (libsource (lib "easyedapro") (part "LED_B"))
    )
    (comp (ref "P1")
      (value "WJ126V-5.0-2P")
      (footprint "easyedapro:CONN-TH_WJ126V-5.0-2P")
      (fields (field (name "Manufacturer") "KANGNEX(康奈克斯电气)"))
      (libsource (lib "easyedapro") (part "WJ126V-5.0-2P"))
    )
    (comp (ref "Q5")
      (value "SI2302")
      (footprint "easyedapro:SOT-23-3_L2.9-W1.3-P1.90-LS2.4-BR")
      (description "类型:1个N沟道;漏源电压(Vdss):20V;连续漏极电流(Id):3A;导通电阻(RDS(on)):50mΩ@4.5V,3A;耗散功率(Pd):1W;阈值电压(Vgs(th)):1V;")
      (fields (field (name "Manufacturer") "YONGYUTAI(永裕泰)"))
      (libsource (lib "easyedapro") (part "SI2302_C2891732"))
    )
    (comp (ref "Q6")
      (value "S8050")
      (footprint "easyedapro:SOT-23-3_L2.9-W1.3-P1.90-LS2.3-BR")
      (description "晶体管类型:NPN;集电极电流(Ic):500mA;集射极击穿电压(Vceo):25V;耗散功率(Pd):300mW;直流电流增益(hFE):120@50mA,1.0V;")
      (fields (field (name "Manufacturer") "R+O(宏嘉诚)"))
      (libsource (lib "easyedapro") (part "S8050_C20069125"))
    )
    (comp (ref "Q7")
      (value "S8050")
      (footprint "easyedapro:SOT-23-3_L2.9-W1.3-P1.90-LS2.4-BR")
      (description "晶体管类型:NPN;集电极电流(Ic):500mA;集射极击穿电压(Vceo):25V;耗散功率(Pd):300mW;直流电流增益(hFE):400@50mA,1V;")
      (fields (field (name "Manufacturer") "Doeshare(德芯)"))
      (libsource (lib "easyedapro") (part "S8050_C2931719"))
    )
    (comp (ref "R110")
      (value "10kΩ")
      (footprint "easyedapro:R0805")
      (fields
        (field (name "Manufacturer Part") "0805W8F1002T5E")
        (field (name "Manufacturer") "UNI-ROYAL(厚声)")
      )
      (libsource (lib "easyedapro") (part "电阻"))
    )
    (comp (ref "R111")
      (value "49.9kΩ")
      (footprint "easyedapro:R0805")
      (description "电阻类型:厚膜电阻;阻值:49.9kΩ;精度:±1%;功率:125mW;工作电压:150V;温度系数:±100ppm/℃;")
      (fields
        (field (name "Manufacturer Part") "0805W8F4992T5E")
        (field (name "Manufacturer") "UNI-ROYAL(厚声)")
      )
      (libsource (lib "easyedapro") (part "电阻"))
    )
    (comp (ref "R112")
      (value "5.1kΩ")
      (footprint "easyedapro:R0805")
      (description "电阻类型:厚膜电阻;阻值:5.1kΩ;精度:±1%;功率:125mW;工作电压:150V;温度系数:±100ppm/℃;")
      (fields
        (field (name "Manufacturer Part") "0805W8F5101T5E")
        (field (name "Manufacturer") "UNI-ROYAL(厚声)")
      )
      (libsource (lib "easyedapro") (part "电阻"))
    )
    (comp (ref "R113")
      (value "10kΩ")
      (footprint "easyedapro:R0805")
      (fields
        (field (name "Manufacturer Part") "0805W8F1002T5E")
        (field (name "Manufacturer") "UNI-ROYAL(厚声)")
      )
      (libsource (lib "easyedapro") (part "电阻"))
    )
    (comp (ref "R114")
      (value "10kΩ")
      (footprint "easyedapro:R0805")
      (fields
        (field (name "Manufacturer Part") "0805W8F1002T5E")
        (field (name "Manufacturer") "UNI-ROYAL(厚声)")
      )
      (libsource (lib "easyedapro") (part "电阻"))
    )
    (comp (ref "R115")
      (value "510Ω")
      (footprint "easyedapro:R0805")
      (description "电阻类型:厚膜电阻;阻值:510Ω;精度:±1%;功率:125mW;工作电压:150V;温度系数:±100ppm/℃;")
      (fields
        (field (name "Manufacturer Part") "0805W8F5100T5E")
        (field (name "Manufacturer") "UNI-ROYAL(厚声)")
      )
      (libsource (lib "easyedapro") (part "电阻"))
    )
    (comp (ref "R116")
      (value "10kΩ")
      (footprint "easyedapro:R0805")
      (fields
        (field (name "Manufacturer Part") "0805W8F1002T5E")
        (field (name "Manufacturer") "UNI-ROYAL(厚声)")
      )
      (libsource (lib "easyedapro") (part "电阻"))
    )
    (comp (ref "R117")
      (value "15kΩ")
      (footprint "easyedapro:R0805")
      (fields
        (field (name "Manufacturer Part") "0805W8F1502T5E")
        (field (name "Manufacturer") "UNI-ROYAL(厚声)")
      )
      (libsource (lib "easyedapro") (part "电阻"))
    )
    (comp (ref "R118")
      (value "360Ω")
      (footprint "easyedapro:R0805")
      (fields
        (field (name "Manufacturer Part") "0805W8J0361T5E")
        (field (name "Manufacturer") "UNI-ROYAL(厚声)")
      )
      (libsource (lib "easyedapro") (part "电阻"))
    )
    (comp (ref "R119")
      (value "360Ω")
      (footprint "easyedapro:R0805")
      (fields
        (field (name "Manufacturer Part") "0805W8J0361T5E")
        (field (name "Manufacturer") "UNI-ROYAL(厚声)")
      )
      (libsource (lib "easyedapro") (part "电阻"))
    )
    (comp (ref "R120")
      (value "120Ω")
      (footprint "easyedapro:R0805")
      (fields
        (field (name "Manufacturer Part") "0805W8F1200T5E")
        (field (name "Manufacturer") "UNI-ROYAL(厚声)")
      )
      (libsource (lib "easyedapro") (part "电阻"))
    )
    (comp (ref "R132")
      (value "10kΩ")
      (footprint "easyedapro:R0805")
      (fields
        (field (name "Manufacturer Part") "0805W8F1002T5E")
        (field (name "Manufacturer") "UNI-ROYAL(厚声)")
      )
      (libsource (lib "easyedapro") (part "电阻"))
    )
    (comp (ref "R133")
      (value "51kΩ")
      (footprint "easyedapro:R0805")
      (fields
        (field (name "Manufacturer Part") "0805W8F5102T5E")
        (field (name "Manufacturer") "UNI-ROYAL(厚声)")
      )
      (libsource (lib "easyedapro") (part "电阻"))
    )
    (comp (ref "R134")
      (value "5.1kΩ")
      (footprint "easyedapro:R0805")
      (description "电阻类型:厚膜电阻;阻值:5.1kΩ;精度:±1%;功率:125mW;工作电压:150V;温度系数:±100ppm/℃;")
      (fields
        (field (name "Manufacturer Part") "0805W8F5101T5E")
        (field (name "Manufacturer") "UNI-ROYAL(厚声)")
      )
      (libsource (lib "easyedapro") (part "电阻"))
    )
    (comp (ref "R135")
      (value "5.1kΩ")
      (footprint "easyedapro:R0805")
      (description "电阻类型:厚膜电阻;阻值:5.1kΩ;精度:±1%;功率:125mW;工作电压:150V;温度系数:±100ppm/℃;")
      (fields
        (field (name "Manufacturer Part") "0805W8F5101T5E")
        (field (name "Manufacturer") "UNI-ROYAL(厚声)")
      )
      (libsource (lib "easyedapro") (part "电阻"))
    )
    (comp (ref "SW13")
      (value "KH-6X6X5H-STM")
      (footprint "easyedapro:SW-SMD_4P-L6.0-W6.0-P4.50-LS9.0_H5.0")
      (description "电路结构:单刀单掷;按钮形状:圆形按钮;安装方式:立贴;开关长度:6mm;开关宽度:6mm;开关高度:5mm;带支架:不带支架;触点电流:50mA;额定电压:12V;工作寿命:8万次;")
      (fields (field (name "Manufacturer") "kinghelm(金航标)"))
      (libsource (lib "easyedapro") (part "KH-6X6X5H-STM"))
    )
    (comp (ref "SW14")
      (value "KH-6X6X5H-STM")
      (footprint "easyedapro:SW-SMD_4P-L6.0-W6.0-P4.50-LS9.0_H5.0")
      (description "电路结构:单刀单掷;按钮形状:圆形按钮;安装方式:立贴;开关长度:6mm;开关宽度:6mm;开关高度:5mm;带支架:不带支架;触点电流:50mA;额定电压:12V;工作寿命:8万次;")
      (fields (field (name "Manufacturer") "kinghelm(金航标)"))
      (libsource (lib "easyedapro") (part "KH-6X6X5H-STM"))
    )
    (comp (ref "U33")
      (value "ESD5451N")
      (footprint "easyedapro:X1-DFN1006-2_L1.0-W0.6-P0.65-BI")
      (description "极性:双向;反向截止电压(Vrwm):5V;钳位电压:13V;峰值脉冲电流(Ipp):5.5A@8/20us;峰值脉冲功率(Ppp):90W@8/20us;击穿电压:8.4V;")
      (fields (field (name "Manufacturer") "TECH PUBLIC(台舟)"))
      (libsource (lib "easyedapro") (part "ESD5451N_C2936977"))
    )
    (comp (ref "U34")
      (value "ESD5451N")
      (footprint "easyedapro:X1-DFN1006-2_L1.0-W0.6-P0.65-BI")
      (description "极性:双向;反向截止电压(Vrwm):5V;钳位电压:13V;峰值脉冲电流(Ipp):5.5A@8/20us;峰值脉冲功率(Ppp):90W@8/20us;击穿电压:8.4V;")
      (fields (field (name "Manufacturer") "TECH PUBLIC(台舟)"))
      (libsource (lib "easyedapro") (part "ESD5451N_C2936977"))
    )
    (comp (ref "U35")
      (value "CH343G")
      (footprint "easyedapro:SOP-16_L10.0-W3.9-P1.27-LS6.0-BL")
      (description "应用功能:USB转UART;USB协议版本:USB 2.0;通道数:-;数据速率:6Mbps;")
      (fields (field (name "Manufacturer") "WCH(南京沁恒)"))
      (libsource (lib "easyedapro") (part "CH343G"))
    )
    (comp (ref "U36")
      (value "XC6206P332MR")
      (footprint "easyedapro:SOT-23-3_L3.0-W1.7-P0.95-LS2.9-BR")
      (description "输出类型:固定;工作电压:8V;输出电压:3.3V;输出电流:250mA;电源纹波抑制比(PSRR):40dB@(1kHz);输出极性:正极;")
      (fields (field (name "Manufacturer") "UMW(友台半导体)"))
      (libsource (lib "easyedapro") (part "XC6206P332MR_C347376"))
    )
    (comp (ref "U37")
      (value "MT9700")
      (footprint "easyedapro:SOT-23-5_L3.0-W1.7-P0.95-LS2.8-BR")
      (description "类型:高侧开关;通道数:1;输入控制逻辑:高电平有效;工作电压:2.4V~5.5V;")
      (fields (field (name "Manufacturer") "西安航天民芯"))
      (libsource (lib "easyedapro") (part "MT9700"))
    )
    (comp (ref "U38")
      (value "ESD5451N")
      (footprint "easyedapro:X1-DFN1006-2_L1.0-W0.6-P0.65-BI")
      (description "极性:双向;反向截止电压(Vrwm):5V;钳位电压:13V;峰值脉冲电流(Ipp):5.5A@8/20us;峰值脉冲功率(Ppp):90W@8/20us;击穿电压:8.4V;")
      (fields (field (name "Manufacturer") "TECH PUBLIC(台舟)"))
      (libsource (lib "easyedapro") (part "ESD5451N_C2936977"))
    )
    (comp (ref "U40")
      (value "ESD5451N")
      (footprint "easyedapro:X1-DFN1006-2_L1.0-W0.6-P0.65-BI")
      (description "极性:双向;反向截止电压(Vrwm):5V;钳位电压:13V;峰值脉冲电流(Ipp):5.5A@8/20us;峰值脉冲功率(Ppp):90W@8/20us;击穿电压:8.4V;")
      (fields (field (name "Manufacturer") "TECH PUBLIC(台舟)"))
      (libsource (lib "easyedapro") (part "ESD5451N_C2936977"))
    )
    (comp (ref "U41")
      (value "AT8563S")
      (footprint "easyedapro:MSOP-8_L3.0-W3.0-P0.65-LS5.0-BL")
      (fields (field (name "Manufacturer") "ANALOGT(芯景)"))
      (libsource (lib "easyedapro") (part "AT8563S_C50341104"))
    )
    (comp (ref "U42")
      (value "BAT54C")
      (footprint "easyedapro:SOT-23-3_L2.9-W1.3-P1.90-LS2.8-BR")
      (description "二极管配置:1对共阴极;正向压降(Vf):1V@100mA;直流反向耐压(Vr):30V;整流电流:200mA;")
      (fields (field (name "Manufacturer") "R+O(宏嘉诚)"))
      (libsource (lib "easyedapro") (part "BAT54C_C22466350"))
    )
    (comp (ref "U43")
      (value "SP3485EEN(UMW)")
      (footprint "easyedapro:SOP-8_L5.0-W4.0-P1.27-LS6.0-BL")
      (description "类型:收发器;数据速率:12Mbps;")
      (fields (field (name "Manufacturer") "UMW(友台半导体)"))
      (libsource (lib "easyedapro") (part "SP3485EEN"))
    )
    (comp (ref "U44")
      (value "MBR0520")
      (footprint "easyedapro:SOD-123_L2.7-W1.6-LS3.7-RD-A")
      (description "二极管配置:独立式;正向压降(Vf):440mV@0.5A;直流反向耐压(Vr):20V;整流电流:500mA;")
      (fields (field (name "Manufacturer") "TWGMC(迪嘉)"))
      (libsource (lib "easyedapro") (part "MBR0520_C5204745"))
    )
    (comp (ref "U46")
      (value "ESD5451N")
      (footprint "easyedapro:X1-DFN1006-2_L1.0-W0.6-P0.65-BI")
      (description "极性:双向;反向截止电压(Vrwm):5V;钳位电压:13V;峰值脉冲电流(Ipp):5.5A@8/20us;峰值脉冲功率(Ppp):90W@8/20us;击穿电压:8.4V;")
      (fields (field (name "Manufacturer") "TECH PUBLIC(台舟)"))
      (libsource (lib "easyedapro") (part "ESD5451N_C2936977"))
    )
    (comp (ref "USBC6")
      (value "TYPE-C-31-M-12")
      (footprint "easyedapro:USB-C_SMD-TYPE-C-31-M-12_1")
      (description "连接器类型:Type-C;协议标准:-;公母:母;安装方式:卧贴;触点数量:16P;端口数量:1;额定电流 - 电源:5A;工作温度:-30°C~+80°C;")
      (fields (field (name "Manufacturer") "韩国韩荣"))
      (libsource (lib "easyedapro") (part "TYPE-C-31-M-12"))
    )
    (comp (ref "USBC8")
      (value "TYPE-C-31-M-12")
      (footprint "easyedapro:USB-C_SMD-TYPE-C-31-M-12_1")
      (description "连接器类型:Type-C;协议标准:-;公母:母;安装方式:卧贴;触点数量:16P;端口数量:1;额定电流 - 电源:5A;工作温度:-30°C~+80°C;")
      (fields (field (name "Manufacturer") "韩国韩荣"))
      (libsource (lib "easyedapro") (part "TYPE-C-31-M-12"))
    )
    (comp (ref "X2")
      (value "32.768kHz")
      (footprint "easyedapro:CRYSTAL-SMD_L3.2-W1.5-1")
      (description "晶振类型:贴片晶振;频率:32.768kHz;常温频差:±20ppm;负载电容:12.5pF;频率稳定度:±30ppm;")
      (fields
        (field (name "Manufacturer Part") "XKXGI-SUA-32.768K")
        (field (name "Manufacturer") "YXC(扬兴晶振)")
      )
      (libsource (lib "easyedapro") (part "XKXGI-SUA-32.768K"))
    )
  )
  (nets
    (net (code "1") (name "CH343_D+") (class "Default")
      (node (ref "U35") (pin "5") (pinfunction "UD+_5") (pintype "unspecified"))
      (node (ref "USBC6") (pin "A6") (pinfunction "DP1_A6") (pintype "unspecified"))
      (node (ref "USBC6") (pin "B6") (pinfunction "DP2_B6") (pintype "unspecified"))
    )
    (net (code "2") (name "CH343_D-") (class "Default")
      (node (ref "U35") (pin "6") (pinfunction "UD-_6") (pintype "unspecified"))
      (node (ref "USBC6") (pin "A7") (pinfunction "DN1_A7") (pintype "unspecified"))
      (node (ref "USBC6") (pin "B7") (pinfunction "DN2_B7") (pintype "unspecified"))
    )
    (net (code "3") (name "CT_INT") (class "Default")
      (node (ref "C125") (pin "2") (pinfunction "2_2") (pintype "input"))
      (node (ref "FPC5") (pin "39") (pinfunction "39_39") (pintype "unspecified"))
      (node (ref "R130") (pin "1") (pinfunction "1_1") (pintype "input"))
      (node (ref "U45") (pin "51") (pinfunction "51_51") (pintype "unspecified"))
    )
    (net (code "4") (name "CT_RST") (class "Default")
      (node (ref "FPC5") (pin "35") (pinfunction "35_35") (pintype "unspecified"))
      (node (ref "R131") (pin "1") (pinfunction "1_1") (pintype "input"))
      (node (ref "U45") (pin "50") (pinfunction "50_50") (pintype "unspecified"))
    )
    (net (code "5") (name "FEL") (class "Default")
      (node (ref "C110") (pin "1") (pinfunction "1_1") (pintype "input"))
      (node (ref "SW14") (pin "1") (pinfunction "1_1") (pintype "unspecified"))
      (node (ref "SW14") (pin "2") (pinfunction "2_2") (pintype "unspecified"))
      (node (ref "U34") (pin "1") (pinfunction "1_1") (pintype "unspecified"))
      (node (ref "U45") (pin "17") (pinfunction "17_17") (pintype "unspecified"))
    )
    (net (code "6") (name "GND") (class "Default")
      (node (ref "BAT1") (pin "1") (pinfunction "1_1") (pintype "input"))
      (node (ref "C100") (pin "2") (pinfunction "2_2") (pintype "input"))
      (node (ref "C101") (pin "2") (pinfunction "2_2") (pintype "unspecified"))
      (node (ref "C102") (pin "1") (pinfunction "1_1") (pintype "input"))
      (node (ref "C108") (pin "2") (pinfunction "2_2") (pintype "input"))
      (node (ref "C109") (pin "2") (pinfunction "2_2") (pintype "input"))
      (node (ref "C110") (pin "2") (pinfunction "2_2") (pintype "input"))
      (node (ref "C111") (pin "1") (pinfunction "1_1") (pintype "input"))
      (node (ref "C112") (pin "2") (pinfunction "2_2") (pintype "input"))
      (node (ref "C113") (pin "2") (pinfunction "2_2") (pintype "input"))
      (node (ref "C114") (pin "1") (pinfunction "1_1") (pintype "input"))
      (node (ref "C115") (pin "1") (pinfunction "1_1") (pintype "input"))
      (node (ref "C116") (pin "1") (pinfunction "1_1") (pintype "input"))
      (node (ref "C117") (pin "1") (pinfunction "1_1") (pintype "input"))
      (node (ref "C118") (pin "2") (pinfunction "2_2") (pintype "input"))
      (node (ref "C119") (pin "2") (pinfunction "2_2") (pintype "input"))
      (node (ref "C120") (pin "1") (pinfunction "1_1") (pintype "input"))
      (node (ref "C121") (pin "1") (pinfunction "1_1") (pintype "input"))
      (node (ref "C122") (pin "2") (pinfunction "2_2") (pintype "input"))
      (node (ref "C123") (pin "1") (pinfunction "1_1") (pintype "input"))
      (node (ref "C124") (pin "2") (pinfunction "2_2") (pintype "input"))
      (node (ref "C125") (pin "1") (pinfunction "1_1") (pintype "input"))
      (node (ref "C127") (pin "1") (pinfunction "1_1") (pintype "input"))
      (node (ref "C85") (pin "2") (pinfunction "2_2") (pintype "unspecified"))
      (node (ref "C86") (pin "2") (pinfunction "2_2") (pintype "input"))
      (node (ref "C87") (pin "1") (pinfunction "1_1") (pintype "input"))
      (node (ref "C89") (pin "1") (pinfunction "1_1") (pintype "input"))
      (node (ref "C90") (pin "2") (pinfunction "2_2") (pintype "input"))
      (node (ref "C91") (pin "2") (pinfunction "2_2") (pintype "unspecified"))
      (node (ref "C92") (pin "1") (pinfunction "1_1") (pintype "input"))
      (node (ref "C94") (pin "1") (pinfunction "1_1") (pintype "input"))
      (node (ref "C95") (pin "2") (pinfunction "2_2") (pintype "input"))
      (node (ref "C96") (pin "2") (pinfunction "2_2") (pintype "unspecified"))
      (node (ref "C97") (pin "1") (pinfunction "1_1") (pintype "input"))
      (node (ref "C99") (pin "1") (pinfunction "1_1") (pintype "input"))
      (node (ref "D10") (pin "2") (pinfunction "2_2") (pintype "unspecified"))
      (node (ref "D11") (pin "2") (pinfunction "2_2") (pintype "unspecified"))
      (node (ref "D13") (pin "3") (pinfunction "3_3") (pintype "unspecified"))
      (node (ref "D9") (pin "2") (pinfunction "2_2") (pintype "unspecified"))
      (node (ref "DC3") (pin "2") (pinfunction "2_2") (pintype "unspecified"))
      (node (ref "DC3") (pin "3") (pinfunction "3_3") (pintype "unspecified"))
      (node (ref "FPC5") (pin "11") (pinfunction "11_11") (pintype "unspecified"))
      (node (ref "FPC5") (pin "20") (pinfunction "20_20") (pintype "unspecified"))
      (node (ref "FPC5") (pin "29") (pinfunction "29_29") (pintype "unspecified"))
      (node (ref "FPC5") (pin "41") (pinfunction "41_41") (pintype "unspecified"))
      (node (ref "FPC5") (pin "42") (pinfunction "42_42") (pintype "unspecified"))
      (node (ref "LED4") (pin "1") (pinfunction "C_1") (pintype "input"))
      (node (ref "Q5") (pin "2") (pinfunction "S_2") (pintype "unspecified"))
      (node (ref "Q6") (pin "2") (pinfunction "E_2") (pintype "input"))
      (node (ref "Q7") (pin "2") (pinfunction "E_2") (pintype "input"))
      (node (ref "R103") (pin "2") (pinfunction "2_2") (pintype "input"))
      (node (ref "R112") (pin "2") (pinfunction "2_2") (pintype "input"))
      (node (ref "R118") (pin "2") (pinfunction "2_2") (pintype "input"))
      (node (ref "R121") (pin "2") (pinfunction "2_2") (pintype "input"))
      (node (ref "R122") (pin "2") (pinfunction "2_2") (pintype "input"))
      (node (ref "R123") (pin "2") (pinfunction "2_2") (pintype "input"))
      (node (ref "R124") (pin "2") (pinfunction "2_2") (pintype "input"))
      (node (ref "R126") (pin "2") (pinfunction "2_2") (pintype "input"))
      (node (ref "R127") (pin "2") (pinfunction "2_2") (pintype "input"))
      (node (ref "R133") (pin "2") (pinfunction "2_2") (pintype "input"))
      (node (ref "R134") (pin "1") (pinfunction "1_1") (pintype "input"))
      (node (ref "R135") (pin "1") (pinfunction "1_1") (pintype "input"))
      (node (ref "R93") (pin "2") (pinfunction "2_2") (pintype "input"))
      (node (ref "R96") (pin "2") (pinfunction "2_2") (pintype "input"))
      (node (ref "R99") (pin "2") (pinfunction "2_2") (pintype "input"))
      (node (ref "SW13") (pin "3") (pinfunction "3_3") (pintype "unspecified"))
      (node (ref "SW13") (pin "4") (pinfunction "4_4") (pintype "unspecified"))
      (node (ref "SW14") (pin "3") (pinfunction "3_3") (pintype "unspecified"))
      (node (ref "SW14") (pin "4") (pinfunction "4_4") (pintype "unspecified"))
      (node (ref "U27") (pin "2") (pinfunction "A_2") (pintype "unspecified"))
      (node (ref "U29") (pin "1") (pinfunction "GND_1") (pintype "unspecified"))
      (node (ref "U30") (pin "1") (pinfunction "GND_1") (pintype "unspecified"))
      (node (ref "U31") (pin "1") (pinfunction "GND_1") (pintype "unspecified"))
      (node (ref "U33") (pin "2") (pinfunction "2_2") (pintype "unspecified"))
      (node (ref "U34") (pin "2") (pinfunction "2_2") (pintype "unspecified"))
      (node (ref "U35") (pin "1") (pinfunction "GND_1") (pintype "unspecified"))
      (node (ref "U36") (pin "1") (pinfunction "VSS_1") (pintype "unspecified"))
      (node (ref "U37") (pin "2") (pinfunction "GND_2") (pintype "unspecified"))
      (node (ref "U38") (pin "2") (pinfunction "2_2") (pintype "unspecified"))
      (node (ref "U40") (pin "1") (pinfunction "1_1") (pintype "unspecified"))
      (node (ref "U41") (pin "4") (pinfunction "VSS_4") (pintype "unspecified"))
      (node (ref "U43") (pin "5") (pinfunction "GND_5") (pintype "unspecified"))
      (node (ref "U45") (pin "103") (pinfunction "103_103") (pintype "unspecified"))
      (node (ref "U45") (pin "11") (pinfunction "11_11") (pintype "unspecified"))
      (node (ref "U45") (pin "118") (pinfunction "118_118") (pintype "unspecified"))
      (node (ref "U45") (pin "123") (pinfunction "123_123") (pintype "unspecified"))
      (node (ref "U45") (pin "127") (pinfunction "127_127") (pintype "unspecified"))
      (node (ref "U45") (pin "15") (pinfunction "15_15") (pintype "unspecified"))
      (node (ref "U45") (pin "21") (pinfunction "21_21") (pintype "unspecified"))
      (node (ref "U45") (pin "24") (pinfunction "24_24") (pintype "unspecified"))
      (node (ref "U45") (pin "32") (pinfunction "32_32") (pintype "unspecified"))
      (node (ref "U45") (pin "4") (pinfunction "4_4") (pintype "unspecified"))
      (node (ref "U45") (pin "5") (pinfunction "5_5") (pintype "unspecified"))
      (node (ref "U45") (pin "52") (pinfunction "52_52") (pintype "unspecified"))
      (node (ref "U45") (pin "74") (pinfunction "74_74") (pintype "unspecified"))
      (node (ref "U45") (pin "8") (pinfunction "8_8") (pintype "unspecified"))
      (node (ref "U45") (pin "85") (pinfunction "85_85") (pintype "unspecified"))
      (node (ref "U45") (pin "96") (pinfunction "96_96") (pintype "unspecified"))
      (node (ref "U46") (pin "2") (pinfunction "2_2") (pintype "unspecified"))
      (node (ref "USBC6") (pin "1") (pinfunction "EH_1") (pintype "unspecified"))
      (node (ref "USBC6") (pin "2") (pinfunction "EH_2") (pintype "unspecified"))
      (node (ref "USBC6") (pin "3") (pinfunction "EH_3") (pintype "unspecified"))
      (node (ref "USBC6") (pin "4") (pinfunction "EH_4") (pintype "unspecified"))
      (node (ref "USBC6") (pin "A1B12") (pinfunction "GND_A1B12") (pintype "unspecified"))
      (node (ref "USBC6") (pin "B1A12") (pinfunction "GND_B1A12") (pintype "unspecified"))
      (node (ref "USBC8") (pin "1") (pinfunction "EH_1") (pintype "unspecified"))
      (node (ref "USBC8") (pin "2") (pinfunction "EH_2") (pintype "unspecified"))
      (node (ref "USBC8") (pin "3") (pinfunction "EH_3") (pintype "unspecified"))
      (node (ref "USBC8") (pin "4") (pinfunction "EH_4") (pintype "unspecified"))
      (node (ref "USBC8") (pin "A1B12") (pinfunction "GND_A1B12") (pintype "unspecified"))
      (node (ref "USBC8") (pin "B1A12") (pinfunction "GND_B1A12") (pintype "unspecified"))
    )
    (net (code "7") (name "I2C2-SCL") (class "Default")
      (node (ref "FPC5") (pin "38") (pinfunction "38_38") (pintype "unspecified"))
      (node (ref "R128") (pin "1") (pinfunction "1_1") (pintype "input"))
      (node (ref "U45") (pin "104") (pinfunction "104_104") (pintype "unspecified"))
    )
    (net (code "8") (name "I2C2-SDA") (class "Default")
      (node (ref "FPC5") (pin "36") (pinfunction "36_36") (pintype "unspecified"))
      (node (ref "R129") (pin "1") (pinfunction "1_1") (pintype "input"))
      (node (ref "U45") (pin "105") (pinfunction "105_105") (pintype "unspecified"))
    )
    (net (code "9") (name "I2C3-SCL") (class "Default")
      (node (ref "R113") (pin "1") (pinfunction "1_1") (pintype "input"))
      (node (ref "U41") (pin "6") (pinfunction "SCL_6") (pintype "unspecified"))
      (node (ref "U45") (pin "54") (pinfunction "54_54") (pintype "unspecified"))
    )
    (net (code "10") (name "I2C3-SDA") (class "Default")
      (node (ref "R114") (pin "1") (pinfunction "1_1") (pintype "input"))
      (node (ref "U41") (pin "5") (pinfunction "SDA_5") (pintype "unspecified"))
      (node (ref "U45") (pin "53") (pinfunction "53_53") (pintype "unspecified"))
    )
    (net (code "11") (name "LCD-CLK") (class "Default")
      (node (ref "FPC5") (pin "30") (pinfunction "30_30") (pintype "unspecified"))
      (node (ref "U45") (pin "94") (pinfunction "94_94") (pintype "unspecified"))
    )
    (net (code "12") (name "LCD-DATA0") (class "Default")
      (node (ref "FPC5") (pin "21") (pinfunction "21_21") (pintype "unspecified"))
      (node (ref "R121") (pin "1") (pinfunction "1_1") (pintype "input"))
    )
    (net (code "13") (name "LCD-DATA1") (class "Default")
      (node (ref "FPC5") (pin "22") (pinfunction "22_22") (pintype "unspecified"))
      (node (ref "R122") (pin "1") (pinfunction "1_1") (pintype "input"))
    )
    (net (code "14") (name "LCD-DATA2") (class "Default")
      (node (ref "FPC5") (pin "23") (pinfunction "23_23") (pintype "unspecified"))
      (node (ref "U45") (pin "75") (pinfunction "75_75") (pintype "unspecified"))
    )
    (net (code "15") (name "LCD-DATA3") (class "Default")
      (node (ref "FPC5") (pin "24") (pinfunction "24_24") (pintype "unspecified"))
      (node (ref "U45") (pin "76") (pinfunction "76_76") (pintype "unspecified"))
    )
    (net (code "16") (name "LCD-DATA4") (class "Default")
      (node (ref "FPC5") (pin "25") (pinfunction "25_25") (pintype "unspecified"))
      (node (ref "U45") (pin "77") (pinfunction "77_77") (pintype "unspecified"))
    )
    (net (code "17") (name "LCD-DATA5") (class "Default")
      (node (ref "FPC5") (pin "26") (pinfunction "26_26") (pintype "unspecified"))
      (node (ref "U45") (pin "78") (pinfunction "78_78") (pintype "unspecified"))
    )
    (net (code "18") (name "LCD-DATA6") (class "Default")
      (node (ref "FPC5") (pin "27") (pinfunction "27_27") (pintype "unspecified"))
      (node (ref "U45") (pin "79") (pinfunction "79_79") (pintype "unspecified"))
    )
    (net (code "19") (name "LCD-DATA7") (class "Default")
      (node (ref "FPC5") (pin "28") (pinfunction "28_28") (pintype "unspecified"))
      (node (ref "U45") (pin "80") (pinfunction "80_80") (pintype "unspecified"))
    )
    (net (code "20") (name "LCD-DATA8") (class "Default")
      (node (ref "FPC5") (pin "12") (pinfunction "12_12") (pintype "unspecified"))
      (node (ref "R123") (pin "1") (pinfunction "1_1") (pintype "input"))
    )
    (net (code "21") (name "LCD-DATA9") (class "Default")
      (node (ref "FPC5") (pin "13") (pinfunction "13_13") (pintype "unspecified"))
      (node (ref "R124") (pin "1") (pinfunction "1_1") (pintype "input"))
    )
    (net (code "22") (name "LCD-DATA10") (class "Default")
      (node (ref "FPC5") (pin "14") (pinfunction "14_14") (pintype "unspecified"))
      (node (ref "U45") (pin "81") (pinfunction "81_81") (pintype "unspecified"))
    )
    (net (code "23") (name "LCD-DATA11") (class "Default")
      (node (ref "FPC5") (pin "15") (pinfunction "15_15") (pintype "unspecified"))
      (node (ref "U45") (pin "82") (pinfunction "82_82") (pintype "unspecified"))
    )
    (net (code "24") (name "LCD-DATA12") (class "Default")
      (node (ref "FPC5") (pin "16") (pinfunction "16_16") (pintype "unspecified"))
      (node (ref "U45") (pin "83") (pinfunction "83_83") (pintype "unspecified"))
    )
    (net (code "25") (name "LCD-DATA13") (class "Default")
      (node (ref "FPC5") (pin "17") (pinfunction "17_17") (pintype "unspecified"))
      (node (ref "U45") (pin "84") (pinfunction "84_84") (pintype "unspecified"))
    )
    (net (code "26") (name "LCD-DATA14") (class "Default")
      (node (ref "FPC5") (pin "18") (pinfunction "18_18") (pintype "unspecified"))
      (node (ref "U45") (pin "86") (pinfunction "86_86") (pintype "unspecified"))
    )
    (net (code "27") (name "LCD-DATA15") (class "Default")
      (node (ref "FPC5") (pin "19") (pinfunction "19_19") (pintype "unspecified"))
      (node (ref "U45") (pin "87") (pinfunction "87_87") (pintype "unspecified"))
    )
    (net (code "28") (name "LCD-DATA16") (class "Default")
      (node (ref "FPC5") (pin "3") (pinfunction "3_3") (pintype "unspecified"))
      (node (ref "R127") (pin "1") (pinfunction "1_1") (pintype "input"))
    )
    (net (code "29") (name "LCD-DATA17") (class "Default")
      (node (ref "FPC5") (pin "4") (pinfunction "4_4") (pintype "unspecified"))
      (node (ref "R126") (pin "1") (pinfunction "1_1") (pintype "input"))
    )
    (net (code "30") (name "LCD-DATA18") (class "Default")
      (node (ref "FPC5") (pin "5") (pinfunction "5_5") (pintype "unspecified"))
      (node (ref "U45") (pin "88") (pinfunction "88_88") (pintype "unspecified"))
    )
    (net (code "31") (name "LCD-DATA19") (class "Default")
      (node (ref "FPC5") (pin "6") (pinfunction "6_6") (pintype "unspecified"))
      (node (ref "U45") (pin "89") (pinfunction "89_89") (pintype "unspecified"))
    )
    (net (code "32") (name "LCD-DATA20") (class "Default")
      (node (ref "FPC5") (pin "7") (pinfunction "7_7") (pintype "unspecified"))
      (node (ref "U45") (pin "90") (pinfunction "90_90") (pintype "unspecified"))
    )
    (net (code "33") (name "LCD-DATA21") (class "Default")
      (node (ref "FPC5") (pin "8") (pinfunction "8_8") (pintype "unspecified"))
      (node (ref "U45") (pin "91") (pinfunction "91_91") (pintype "unspecified"))
    )
    (net (code "34") (name "LCD-DATA22") (class "Default")
      (node (ref "FPC5") (pin "9") (pinfunction "9_9") (pintype "unspecified"))
      (node (ref "U45") (pin "92") (pinfunction "92_92") (pintype "unspecified"))
    )
    (net (code "35") (name "LCD-DATA23") (class "Default")
      (node (ref "FPC5") (pin "10") (pinfunction "10_10") (pintype "unspecified"))
      (node (ref "U45") (pin "93") (pinfunction "93_93") (pintype "unspecified"))
    )
    (net (code "36") (name "LCD-DE") (class "Default")
      (node (ref "FPC5") (pin "33") (pinfunction "33_33") (pintype "unspecified"))
      (node (ref "U45") (pin "95") (pinfunction "95_95") (pintype "unspecified"))
    )
    (net (code "37") (name "LCD-HSYNC") (class "Default")
      (node (ref "FPC5") (pin "31") (pinfunction "31_31") (pintype "unspecified"))
      (node (ref "U45") (pin "73") (pinfunction "73_73") (pintype "unspecified"))
    )
    (net (code "38") (name "LCD-VSYNC") (class "Default")
      (node (ref "FPC5") (pin "32") (pinfunction "32_32") (pintype "unspecified"))
      (node (ref "U45") (pin "72") (pinfunction "72_72") (pintype "unspecified"))
    )
    (net (code "39") (name "LCD_RST") (class "Default")
      (node (ref "FPC5") (pin "40") (pinfunction "40_40") (pintype "unspecified"))
      (node (ref "U45") (pin "40") (pinfunction "40_40") (pintype "unspecified"))
    )
    (net (code "40") (name "Net-(D12-K)") (class "Default")
      (node (ref "D12") (pin "1") (pinfunction "K_1") (pintype "unspecified"))
      (node (ref "U40") (pin "2") (pinfunction "2_2") (pintype "unspecified"))
      (node (ref "USBC8") (pin "A5") (pinfunction "CC1_A5") (pintype "unspecified"))
      (node (ref "USBC8") (pin "B5") (pinfunction "CC2_B5") (pintype "unspecified"))
    )
    (net (code "41") (name "Net-(DC3-Pad1)") (class "Default")
      (node (ref "DC3") (pin "1") (pinfunction "1_1") (pintype "unspecified"))
      (node (ref "SW12") (pin "1") (pinfunction "1_1") (pintype "unspecified"))
    )
    (net (code "42") (name "Net-(F1-Pad1)") (class "Default")
      (node (ref "F1") (pin "1") (pinfunction "1_1") (pintype "unspecified"))
      (node (ref "SW12") (pin "2") (pinfunction "2_2") (pintype "unspecified"))
    )
    (net (code "43") (name "Net-(LED4-A)") (class "Default")
      (node (ref "LED4") (pin "2") (pinfunction "A_2") (pintype "input"))
      (node (ref "R109") (pin "2") (pinfunction "2_2") (pintype "input"))
    )
    (net (code "44") (name "Net-(LED5-A)") (class "Default")
      (node (ref "LED5") (pin "2") (pinfunction "A_2") (pintype "input"))
      (node (ref "R115") (pin "2") (pinfunction "2_2") (pintype "input"))
    )
    (net (code "45") (name "Net-(LED5-C)") (class "Default")
      (node (ref "LED5") (pin "1") (pinfunction "C_1") (pintype "input"))
      (node (ref "Q7") (pin "3") (pinfunction "C_3") (pintype "input"))
    )
    (net (code "46") (name "Net-(Q3-B)") (class "Default")
      (node (ref "Q3") (pin "1") (pinfunction "B_1") (pintype "input"))
      (node (ref "R91") (pin "2") (pinfunction "2_2") (pintype "input"))
    )
    (net (code "47") (name "Net-(Q3-C)") (class "Default")
      (node (ref "C84") (pin "1") (pinfunction "1_1") (pintype "input"))
      (node (ref "Q3") (pin "3") (pinfunction "C_3") (pintype "input"))
      (node (ref "R93") (pin "1") (pinfunction "1_1") (pintype "input"))
      (node (ref "R94") (pin "1") (pinfunction "1_1") (pintype "input"))
      (node (ref "U28") (pin "2") (pinfunction "A_2") (pintype "unspecified"))
    )
    (net (code "48") (name "Net-(Q3-E)") (class "Default")
      (node (ref "C84") (pin "2") (pinfunction "2_2") (pintype "input"))
      (node (ref "F1") (pin "2") (pinfunction "2_2") (pintype "unspecified"))
      (node (ref "Q3") (pin "2") (pinfunction "E_2") (pintype "input"))
      (node (ref "Q4") (pin "1") (pinfunction "S_1") (pintype "unspecified"))
      (node (ref "Q4") (pin "2") (pinfunction "S_2") (pintype "unspecified"))
      (node (ref "Q4") (pin "3") (pinfunction "S_3") (pintype "unspecified"))
      (node (ref "R92") (pin "2") (pinfunction "2_2") (pintype "input"))
      (node (ref "U28") (pin "1") (pinfunction "K_1") (pintype "unspecified"))
    )
    (net (code "49") (name "Net-(Q4-G)") (class "Default")
      (node (ref "Q4") (pin "4") (pinfunction "G_4") (pintype "unspecified"))
      (node (ref "R94") (pin "2") (pinfunction "2_2") (pintype "input"))
    )
    (net (code "50") (name "Net-(Q5-D)") (class "Default")
      (node (ref "Q5") (pin "3") (pinfunction "D_3") (pintype "unspecified"))
      (node (ref "R110") (pin "1") (pinfunction "1_1") (pintype "input"))
      (node (ref "U37") (pin "4") (pinfunction "EN_4") (pintype "unspecified"))
    )
    (net (code "51") (name "Net-(Q6-B)") (class "Default")
      (node (ref "C123") (pin "2") (pinfunction "2_2") (pintype "input"))
      (node (ref "Q6") (pin "1") (pinfunction "B_1") (pintype "input"))
      (node (ref "R117") (pin "2") (pinfunction "2_2") (pintype "input"))
      (node (ref "U44") (pin "2") (pinfunction "A_2") (pintype "unspecified"))
    )
    (net (code "52") (name "Net-(Q6-C)") (class "Default")
      (node (ref "Q6") (pin "3") (pinfunction "C_3") (pintype "input"))
      (node (ref "R116") (pin "1") (pinfunction "1_1") (pintype "input"))
      (node (ref "U43") (pin "2") (pinfunction "#RE_2") (pintype "unspecified"))
      (node (ref "U43") (pin "3") (pinfunction "DE_3") (pintype "unspecified"))
    )
    (net (code "53") (name "Net-(Q7-B)") (class "Default")
      (node (ref "Q7") (pin "1") (pinfunction "B_1") (pintype "input"))
      (node (ref "R132") (pin "2") (pinfunction "2_2") (pintype "input"))
    )
    (net (code "54") (name "Net-(U27-K)") (class "Default")
      (node (ref "R91") (pin "1") (pinfunction "1_1") (pintype "input"))
      (node (ref "R92") (pin "1") (pinfunction "1_1") (pintype "input"))
      (node (ref "U27") (pin "1") (pinfunction "K_1") (pintype "unspecified"))
    )
    (net (code "55") (name "Net-(U29-BST)") (class "Default")
      (node (ref "C88") (pin "1") (pinfunction "1_1") (pintype "input"))
      (node (ref "U29") (pin "6") (pinfunction "BST_6") (pintype "unspecified"))
    )
    (net (code "56") (name "Net-(U29-EN)") (class "Default")
      (node (ref "R95") (pin "2") (pinfunction "2_2") (pintype "input"))
      (node (ref "U29") (pin "5") (pinfunction "EN_5") (pintype "unspecified"))
    )
    (net (code "57") (name "Net-(U29-FB)") (class "Default")
      (node (ref "R96") (pin "1") (pinfunction "1_1") (pintype "input"))
      (node (ref "R97") (pin "2") (pinfunction "2_2") (pintype "input"))
      (node (ref "U29") (pin "4") (pinfunction "FB_4") (pintype "unspecified"))
    )
    (net (code "58") (name "Net-(U29-SW)") (class "Default")
      (node (ref "C88") (pin "2") (pinfunction "2_2") (pintype "input"))
      (node (ref "L7") (pin "1") (pinfunction "1_1") (pintype "unspecified"))
      (node (ref "U29") (pin "2") (pinfunction "SW_2") (pintype "unspecified"))
    )
    (net (code "59") (name "Net-(U30-BST)") (class "Default")
      (node (ref "C93") (pin "1") (pinfunction "1_1") (pintype "input"))
      (node (ref "U30") (pin "6") (pinfunction "BST_6") (pintype "unspecified"))
    )
    (net (code "60") (name "Net-(U30-EN)") (class "Default")
      (node (ref "R101") (pin "2") (pinfunction "2_2") (pintype "input"))
      (node (ref "R98") (pin "2") (pinfunction "2_2") (pintype "input"))
      (node (ref "U30") (pin "5") (pinfunction "EN_5") (pintype "unspecified"))
    )
    (net (code "61") (name "Net-(U30-FB)") (class "Default")
      (node (ref "R100") (pin "2") (pinfunction "2_2") (pintype "input"))
      (node (ref "R99") (pin "1") (pinfunction "1_1") (pintype "input"))
      (node (ref "U30") (pin "4") (pinfunction "FB_4") (pintype "unspecified"))
    )
    (net (code "62") (name "Net-(U30-SW)") (class "Default")
      (node (ref "C93") (pin "2") (pinfunction "2_2") (pintype "input"))
      (node (ref "L8") (pin "1") (pinfunction "1_1") (pintype "unspecified"))
      (node (ref "U30") (pin "2") (pinfunction "SW_2") (pintype "unspecified"))
    )
    (net (code "63") (name "Net-(U31-BST)") (class "Default")
      (node (ref "C98") (pin "1") (pinfunction "1_1") (pintype "input"))
      (node (ref "U31") (pin "6") (pinfunction "BST_6") (pintype "unspecified"))
    )
    (net (code "64") (name "Net-(U31-EN)") (class "Default")
      (node (ref "R102") (pin "2") (pinfunction "2_2") (pintype "input"))
      (node (ref "R105") (pin "2") (pinfunction "2_2") (pintype "input"))
      (node (ref "U31") (pin "5") (pinfunction "EN_5") (pintype "unspecified"))
    )
    (net (code "65") (name "Net-(U31-FB)") (class "Default")
      (node (ref "R103") (pin "1") (pinfunction "1_1") (pintype "input"))
      (node (ref "R104") (pin "2") (pinfunction "2_2") (pintype "input"))
      (node (ref "U31") (pin "4") (pinfunction "FB_4") (pintype "unspecified"))
    )
    (net (code "66") (name "Net-(U31-SW)") (class "Default")
      (node (ref "C98") (pin "2") (pinfunction "2_2") (pintype "input"))
      (node (ref "L9") (pin "1") (pinfunction "1_1") (pintype "unspecified"))
      (node (ref "U31") (pin "2") (pinfunction "SW_2") (pintype "unspecified"))
    )
    (net (code "67") (name "Net-(U35-V3)") (class "Default")
      (node (ref "C111") (pin "2") (pinfunction "2_2") (pintype "input"))
      (node (ref "U35") (pin "4") (pinfunction "V3_4") (pintype "unspecified"))
    )
    (net (code "68") (name "Net-(U37-SET)") (class "Default")
      (node (ref "R112") (pin "1") (pinfunction "1_1") (pintype "input"))
      (node (ref "U37") (pin "3") (pinfunction "SET_3") (pintype "unspecified"))
    )
    (net (code "69") (name "Net-(U41-OSCI)") (class "Default")
      (node (ref "C120") (pin "2") (pinfunction "2_2") (pintype "input"))
      (node (ref "U41") (pin "1") (pinfunction "OSCI_1") (pintype "unspecified"))
      (node (ref "X2") (pin "2") (pinfunction "OSC2_2") (pintype "input"))
    )
    (net (code "70") (name "Net-(U41-OSCO)") (class "Default")
      (node (ref "C121") (pin "2") (pinfunction "2_2") (pintype "input"))
      (node (ref "U41") (pin "2") (pinfunction "OSCO_2") (pintype "unspecified"))
      (node (ref "X2") (pin "1") (pinfunction "OSC1_1") (pintype "input"))
    )
    (net (code "71") (name "Net-(U41-VDD)") (class "Default")
      (node (ref "C122") (pin "1") (pinfunction "1_1") (pintype "input"))
      (node (ref "U41") (pin "8") (pinfunction "VDD_8") (pintype "unspecified"))
      (node (ref "U42") (pin "3") (pinfunction "K_3") (pintype "unspecified"))
    )
    (net (code "72") (name "Net-(USBC6-CC1)") (class "Default")
      (node (ref "R134") (pin "2") (pinfunction "2_2") (pintype "input"))
      (node (ref "USBC6") (pin "A5") (pinfunction "CC1_A5") (pintype "unspecified"))
    )
    (net (code "73") (name "Net-(USBC6-CC2)") (class "Default")
      (node (ref "R135") (pin "2") (pinfunction "2_2") (pintype "input"))
      (node (ref "USBC6") (pin "B5") (pinfunction "CC2_B5") (pintype "unspecified"))
    )
    (net (code "74") (name "PWM3") (class "Default")
      (node (ref "FPC5") (pin "34") (pinfunction "34_34") (pintype "unspecified"))
      (node (ref "U45") (pin "41") (pinfunction "41_41") (pintype "unspecified"))
    )
    (net (code "75") (name "PWR_ON") (class "Default")
      (node (ref "R101") (pin "1") (pinfunction "1_1") (pintype "input"))
      (node (ref "R105") (pin "1") (pinfunction "1_1") (pintype "input"))
      (node (ref "U45") (pin "20") (pinfunction "20_20") (pintype "unspecified"))
    )
    (net (code "76") (name "RESET") (class "Default")
      (node (ref "C109") (pin "1") (pinfunction "1_1") (pintype "input"))
      (node (ref "SW13") (pin "1") (pinfunction "1_1") (pintype "unspecified"))
      (node (ref "SW13") (pin "2") (pinfunction "2_2") (pintype "unspecified"))
      (node (ref "U33") (pin "1") (pinfunction "1_1") (pintype "unspecified"))
      (node (ref "U45") (pin "19") (pinfunction "19_19") (pintype "unspecified"))
    )
    (net (code "77") (name "RS485_1_A") (class "Default")
      (node (ref "D13") (pin "2") (pinfunction "2_2") (pintype "unspecified"))
      (node (ref "P1") (pin "1") (pinfunction "1_1") (pintype "input"))
      (node (ref "R119") (pin "2") (pinfunction "2_2") (pintype "input"))
      (node (ref "R120") (pin "1") (pinfunction "1_1") (pintype "input"))
      (node (ref "U43") (pin "6") (pinfunction "A_6") (pintype "unspecified"))
    )
    (net (code "78") (name "RS485_1_B") (class "Default")
      (node (ref "D13") (pin "1") (pinfunction "1_1") (pintype "unspecified"))
      (node (ref "P1") (pin "2") (pinfunction "2_2") (pintype "input"))
      (node (ref "R118") (pin "1") (pinfunction "1_1") (pintype "input"))
      (node (ref "R120") (pin "2") (pinfunction "2_2") (pintype "input"))
      (node (ref "U43") (pin "7") (pinfunction "B_7") (pintype "unspecified"))
    )
    (net (code "79") (name "SPI1-HOLD") (class "Default")
      (node (ref "R132") (pin "1") (pinfunction "1_1") (pintype "input"))
      (node (ref "R133") (pin "1") (pinfunction "1_1") (pintype "input"))
      (node (ref "U45") (pin "106") (pinfunction "106_106") (pintype "unspecified"))
    )
    (net (code "80") (name "UART0_RX") (class "Default")
      (node (ref "U35") (pin "2") (pinfunction "TXD_2") (pintype "unspecified"))
      (node (ref "U45") (pin "33") (pinfunction "33_33") (pintype "unspecified"))
    )
    (net (code "81") (name "UART0_TX") (class "Default")
      (node (ref "U35") (pin "3") (pinfunction "RXD_3") (pintype "unspecified"))
      (node (ref "U45") (pin "34") (pinfunction "34_34") (pintype "unspecified"))
    )
    (net (code "82") (name "UART4_RX") (class "Default")
      (node (ref "U43") (pin "1") (pinfunction "RO_1") (pintype "unspecified"))
      (node (ref "U45") (pin "48") (pinfunction "48_48") (pintype "unspecified"))
    )
    (net (code "83") (name "UART4_TX") (class "Default")
      (node (ref "R117") (pin "1") (pinfunction "1_1") (pintype "input"))
      (node (ref "U43") (pin "4") (pinfunction "DI_4") (pintype "unspecified"))
      (node (ref "U44") (pin "1") (pinfunction "K_1") (pintype "unspecified"))
      (node (ref "U45") (pin "49") (pinfunction "49_49") (pintype "unspecified"))
    )
    (net (code "84") (name "UART_3.3") (class "Default")
      (node (ref "C112") (pin "1") (pinfunction "1_1") (pintype "input"))
      (node (ref "C113") (pin "1") (pinfunction "1_1") (pintype "input"))
      (node (ref "C114") (pin "2") (pinfunction "2_2") (pintype "input"))
      (node (ref "U35") (pin "15") (pinfunction "VIO_15") (pintype "unspecified"))
      (node (ref "U36") (pin "2") (pinfunction "VOUT_2") (pintype "unspecified"))
    )
    (net (code "85") (name "USB0_N") (class "Default")
      (node (ref "U38") (pin "1") (pinfunction "1_1") (pintype "unspecified"))
      (node (ref "U45") (pin "121") (pinfunction "121_121") (pintype "unspecified"))
      (node (ref "USBC8") (pin "A7") (pinfunction "DN1_A7") (pintype "unspecified"))
      (node (ref "USBC8") (pin "B7") (pinfunction "DN2_B7") (pintype "unspecified"))
    )
    (net (code "86") (name "USB0_P") (class "Default")
      (node (ref "U45") (pin "122") (pinfunction "122_122") (pintype "unspecified"))
      (node (ref "U46") (pin "1") (pinfunction "1_1") (pintype "unspecified"))
      (node (ref "USBC8") (pin "A6") (pinfunction "DP1_A6") (pintype "unspecified"))
      (node (ref "USBC8") (pin "B6") (pinfunction "DP2_B6") (pintype "unspecified"))
    )
    (net (code "87") (name "USB_ID") (class "Default")
      (node (ref "D12") (pin "2") (pinfunction "A_2") (pintype "unspecified"))
      (node (ref "Q5") (pin "1") (pinfunction "G_1") (pintype "unspecified"))
      (node (ref "R111") (pin "2") (pinfunction "2_2") (pintype "input"))
      (node (ref "U45") (pin "35") (pinfunction "35_35") (pintype "unspecified"))
    )
    (net (code "88") (name "VBAT") (class "Default")
      (node (ref "BAT1") (pin "2") (pinfunction "2_2") (pintype "input"))
      (node (ref "C108") (pin "1") (pinfunction "1_1") (pintype "input"))
      (node (ref "U42") (pin "1") (pinfunction "A_1") (pintype "unspecified"))
    )
    (net (code "89") (name "VCC3V3_CORE") (class "Default")
      (node (ref "C91") (pin "1") (pinfunction "1_1") (pintype "unspecified"))
      (node (ref "C92") (pin "2") (pinfunction "2_2") (pintype "input"))
      (node (ref "D9") (pin "1") (pinfunction "1_1") (pintype "unspecified"))
      (node (ref "L7") (pin "2") (pinfunction "2_2") (pintype "unspecified"))
      (node (ref "R97") (pin "1") (pinfunction "1_1") (pintype "input"))
    )
    (net (code "90") (name "VCC3V3_SYS") (class "Default")
      (node (ref "C124") (pin "1") (pinfunction "1_1") (pintype "input"))
      (node (ref "C96") (pin "1") (pinfunction "1_1") (pintype "unspecified"))
      (node (ref "C97") (pin "2") (pinfunction "2_2") (pintype "input"))
      (node (ref "D10") (pin "1") (pinfunction "1_1") (pintype "unspecified"))
      (node (ref "L8") (pin "2") (pinfunction "2_2") (pintype "unspecified"))
      (node (ref "R100") (pin "1") (pinfunction "1_1") (pintype "input"))
      (node (ref "R109") (pin "1") (pinfunction "1_1") (pintype "input"))
      (node (ref "R111") (pin "1") (pinfunction "1_1") (pintype "input"))
      (node (ref "R113") (pin "2") (pinfunction "2_2") (pintype "input"))
      (node (ref "R114") (pin "2") (pinfunction "2_2") (pintype "input"))
      (node (ref "R115") (pin "1") (pinfunction "1_1") (pintype "input"))
      (node (ref "R116") (pin "2") (pinfunction "2_2") (pintype "input"))
      (node (ref "R119") (pin "1") (pinfunction "1_1") (pintype "input"))
      (node (ref "R128") (pin "2") (pinfunction "2_2") (pintype "input"))
      (node (ref "R129") (pin "2") (pinfunction "2_2") (pintype "input"))
      (node (ref "R130") (pin "2") (pinfunction "2_2") (pintype "input"))
      (node (ref "R131") (pin "2") (pinfunction "2_2") (pintype "input"))
      (node (ref "U42") (pin "2") (pinfunction "A_2") (pintype "unspecified"))
      (node (ref "U43") (pin "8") (pinfunction "VCC_8") (pintype "unspecified"))
      (node (ref "U45") (pin "1") (pinfunction "1_1") (pintype "unspecified"))
      (node (ref "U45") (pin "2") (pinfunction "2_2") (pintype "unspecified"))
      (node (ref "U45") (pin "3") (pinfunction "3_3") (pintype "unspecified"))
    )
    (net (code "91") (name "VCC5V_SYS") (class "Default")
      (node (ref "C101") (pin "1") (pinfunction "1_1") (pintype "unspecified"))
      (node (ref "C102") (pin "2") (pinfunction "2_2") (pintype "input"))
      (node (ref "C117") (pin "2") (pinfunction "2_2") (pintype "input"))
      (node (ref "C127") (pin "2") (pinfunction "2_2") (pintype "input"))
      (node (ref "D11") (pin "1") (pinfunction "1_1") (pintype "unspecified"))
      (node (ref "FPC5") (pin "1") (pinfunction "1_1") (pintype "unspecified"))
      (node (ref "FPC5") (pin "2") (pinfunction "2_2") (pintype "unspecified"))
      (node (ref "L9") (pin "2") (pinfunction "2_2") (pintype "unspecified"))
      (node (ref "R104") (pin "1") (pinfunction "1_1") (pintype "input"))
      (node (ref "R110") (pin "2") (pinfunction "2_2") (pintype "input"))
      (node (ref "U37") (pin "5") (pinfunction "VIN_5") (pintype "unspecified"))
    )
    (net (code "92") (name "VCC12V_DCIN") (class "Default")
      (node (ref "C100") (pin "1") (pinfunction "1_1") (pintype "input"))
      (node (ref "C85") (pin "1") (pinfunction "1_1") (pintype "unspecified"))
      (node (ref "C86") (pin "1") (pinfunction "1_1") (pintype "input"))
      (node (ref "C87") (pin "2") (pinfunction "2_2") (pintype "input"))
      (node (ref "C89") (pin "2") (pinfunction "2_2") (pintype "input"))
      (node (ref "C90") (pin "1") (pinfunction "1_1") (pintype "input"))
      (node (ref "C94") (pin "2") (pinfunction "2_2") (pintype "input"))
      (node (ref "C95") (pin "1") (pinfunction "1_1") (pintype "input"))
      (node (ref "C99") (pin "2") (pinfunction "2_2") (pintype "input"))
      (node (ref "Q4") (pin "5") (pinfunction "D_5") (pintype "unspecified"))
      (node (ref "R102") (pin "1") (pinfunction "1_1") (pintype "input"))
      (node (ref "R95") (pin "1") (pinfunction "1_1") (pintype "input"))
      (node (ref "R98") (pin "1") (pinfunction "1_1") (pintype "input"))
      (node (ref "U29") (pin "3") (pinfunction "VIN_3") (pintype "unspecified"))
      (node (ref "U30") (pin "3") (pinfunction "VIN_3") (pintype "unspecified"))
      (node (ref "U31") (pin "3") (pinfunction "VIN_3") (pintype "unspecified"))
    )
    (net (code "93") (name "VCC_USBOTG") (class "Default")
      (node (ref "C118") (pin "1") (pinfunction "1_1") (pintype "input"))
      (node (ref "C119") (pin "1") (pinfunction "1_1") (pintype "input"))
      (node (ref "U37") (pin "1") (pinfunction "VOUT_1") (pintype "unspecified"))
      (node (ref "USBC8") (pin "A4B9") (pinfunction "VBUS_A4B9") (pintype "unspecified"))
      (node (ref "USBC8") (pin "B4A9") (pinfunction "VBUS_B4A9") (pintype "unspecified"))
    )
    (net (code "94") (name "VUSB") (class "Default")
      (node (ref "C115") (pin "2") (pinfunction "2_2") (pintype "input"))
      (node (ref "C116") (pin "2") (pinfunction "2_2") (pintype "input"))
      (node (ref "U35") (pin "16") (pinfunction "VDD5_16") (pintype "unspecified"))
      (node (ref "U35") (pin "7") (pinfunction "VBUS_7") (pintype "unspecified"))
      (node (ref "U36") (pin "3") (pinfunction "VIN_3") (pintype "unspecified"))
      (node (ref "USBC6") (pin "A4B9") (pinfunction "VBUS_A4B9") (pintype "unspecified"))
      (node (ref "USBC6") (pin "B4A9") (pinfunction "VBUS_B4A9") (pintype "unspecified"))
    )
    (net (code "95") (name "unconnected-(FPC5-Pad37)") (class "Default")
      (node (ref "FPC5") (pin "37") (pinfunction "37_37") (pintype "unspecified+no_connect"))
    )
    (net (code "96") (name "unconnected-(SCREW1-Pad1)") (class "Default")
      (node (ref "SCREW1") (pin "1") (pinfunction "1_1") (pintype "input"))
    )
    (net (code "97") (name "unconnected-(SCREW2-Pad1)") (class "Default")
      (node (ref "SCREW2") (pin "1") (pinfunction "1_1") (pintype "input"))
    )
    (net (code "98") (name "unconnected-(SCREW3-Pad1)") (class "Default")
      (node (ref "SCREW3") (pin "1") (pinfunction "1_1") (pintype "input"))
    )
    (net (code "99") (name "unconnected-(SCREW4-Pad1)") (class "Default")
      (node (ref "SCREW4") (pin "1") (pinfunction "1_1") (pintype "input"))
    )
    (net (code "100") (name "unconnected-(SCREW5-Pad1)") (class "Default")
      (node (ref "SCREW5") (pin "1") (pinfunction "1_1") (pintype "input"))
    )
    (net (code "101") (name "unconnected-(SCREW6-Pad1)") (class "Default")
      (node (ref "SCREW6") (pin "1") (pinfunction "1_1") (pintype "input"))
    )
    (net (code "102") (name "unconnected-(SW12-Pad3)") (class "Default")
      (node (ref "SW12") (pin "3") (pinfunction "3_3") (pintype "unspecified+no_connect"))
    )
    (net (code "103") (name "unconnected-(U35-ACT#-Pad8)") (class "Default")
      (node (ref "U35") (pin "8") (pinfunction "ACT#_8") (pintype "unspecified+no_connect"))
    )
    (net (code "104") (name "unconnected-(U35-CTS-Pad13)") (class "Default")
      (node (ref "U35") (pin "13") (pinfunction "CTS_13") (pintype "unspecified+no_connect"))
    )
    (net (code "105") (name "unconnected-(U35-DCD-Pad9)") (class "Default")
      (node (ref "U35") (pin "9") (pinfunction "DCD_9") (pintype "unspecified+no_connect"))
    )
    (net (code "106") (name "unconnected-(U35-DSR-Pad12)") (class "Default")
      (node (ref "U35") (pin "12") (pinfunction "DSR_12") (pintype "unspecified+no_connect"))
    )
    (net (code "107") (name "unconnected-(U35-DTR-Pad10)") (class "Default")
      (node (ref "U35") (pin "10") (pinfunction "DTR_10") (pintype "unspecified+no_connect"))
    )
    (net (code "108") (name "unconnected-(U35-RI-Pad14)") (class "Default")
      (node (ref "U35") (pin "14") (pinfunction "RI_14") (pintype "unspecified+no_connect"))
    )
    (net (code "109") (name "unconnected-(U35-RTS-Pad11)") (class "Default")
      (node (ref "U35") (pin "11") (pinfunction "RTS_11") (pintype "unspecified+no_connect"))
    )
    (net (code "110") (name "unconnected-(U41-CLKOUT-Pad7)") (class "Default")
      (node (ref "U41") (pin "7") (pinfunction "CLKOUT_7") (pintype "unspecified+no_connect"))
    )
    (net (code "111") (name "unconnected-(U41-INT#-Pad3)") (class "Default")
      (node (ref "U41") (pin "3") (pinfunction "INT#_3") (pintype "unspecified+no_connect"))
    )
    (net (code "112") (name "unconnected-(U45-Pad6)") (class "Default")
      (node (ref "U45") (pin "6") (pinfunction "6_6") (pintype "unspecified+no_connect"))
    )
    (net (code "113") (name "unconnected-(U45-Pad7)") (class "Default")
      (node (ref "U45") (pin "7") (pinfunction "7_7") (pintype "unspecified+no_connect"))
    )
    (net (code "114") (name "unconnected-(U45-Pad9)") (class "Default")
      (node (ref "U45") (pin "9") (pinfunction "9_9") (pintype "unspecified+no_connect"))
    )
    (net (code "115") (name "unconnected-(U45-Pad10)") (class "Default")
      (node (ref "U45") (pin "10") (pinfunction "10_10") (pintype "unspecified+no_connect"))
    )
    (net (code "116") (name "unconnected-(U45-Pad12)") (class "Default")
      (node (ref "U45") (pin "12") (pinfunction "12_12") (pintype "unspecified+no_connect"))
    )
    (net (code "117") (name "unconnected-(U45-Pad13)") (class "Default")
      (node (ref "U45") (pin "13") (pinfunction "13_13") (pintype "unspecified+no_connect"))
    )
    (net (code "118") (name "unconnected-(U45-Pad14)") (class "Default")
      (node (ref "U45") (pin "14") (pinfunction "14_14") (pintype "unspecified+no_connect"))
    )
    (net (code "119") (name "unconnected-(U45-Pad16)") (class "Default")
      (node (ref "U45") (pin "16") (pinfunction "16_16") (pintype "unspecified+no_connect"))
    )
    (net (code "120") (name "unconnected-(U45-Pad18)") (class "Default")
      (node (ref "U45") (pin "18") (pinfunction "18_18") (pintype "unspecified+no_connect"))
    )
    (net (code "121") (name "unconnected-(U45-Pad22)") (class "Default")
      (node (ref "U45") (pin "22") (pinfunction "22_22") (pintype "unspecified+no_connect"))
    )
    (net (code "122") (name "unconnected-(U45-Pad23)") (class "Default")
      (node (ref "U45") (pin "23") (pinfunction "23_23") (pintype "unspecified+no_connect"))
    )
    (net (code "123") (name "unconnected-(U45-Pad25)") (class "Default")
      (node (ref "U45") (pin "25") (pinfunction "25_25") (pintype "unspecified+no_connect"))
    )
    (net (code "124") (name "unconnected-(U45-Pad26)") (class "Default")
      (node (ref "U45") (pin "26") (pinfunction "26_26") (pintype "unspecified+no_connect"))
    )
    (net (code "125") (name "unconnected-(U45-Pad27)") (class "Default")
      (node (ref "U45") (pin "27") (pinfunction "27_27") (pintype "unspecified+no_connect"))
    )
    (net (code "126") (name "unconnected-(U45-Pad28)") (class "Default")
      (node (ref "U45") (pin "28") (pinfunction "28_28") (pintype "unspecified+no_connect"))
    )
    (net (code "127") (name "unconnected-(U45-Pad29)") (class "Default")
      (node (ref "U45") (pin "29") (pinfunction "29_29") (pintype "unspecified+no_connect"))
    )
    (net (code "128") (name "unconnected-(U45-Pad30)") (class "Default")
      (node (ref "U45") (pin "30") (pinfunction "30_30") (pintype "unspecified+no_connect"))
    )
    (net (code "129") (name "unconnected-(U45-Pad31)") (class "Default")
      (node (ref "U45") (pin "31") (pinfunction "31_31") (pintype "unspecified+no_connect"))
    )
    (net (code "130") (name "unconnected-(U45-Pad36)") (class "Default")
      (node (ref "U45") (pin "36") (pinfunction "36_36") (pintype "unspecified+no_connect"))
    )
    (net (code "131") (name "unconnected-(U45-Pad37)") (class "Default")
      (node (ref "U45") (pin "37") (pinfunction "37_37") (pintype "unspecified+no_connect"))
    )
    (net (code "132") (name "unconnected-(U45-Pad38)") (class "Default")
      (node (ref "U45") (pin "38") (pinfunction "38_38") (pintype "unspecified+no_connect"))
    )
    (net (code "133") (name "unconnected-(U45-Pad39)") (class "Default")
      (node (ref "U45") (pin "39") (pinfunction "39_39") (pintype "unspecified+no_connect"))
    )
    (net (code "134") (name "unconnected-(U45-Pad42)") (class "Default")
      (node (ref "U45") (pin "42") (pinfunction "42_42") (pintype "unspecified+no_connect"))
    )
    (net (code "135") (name "unconnected-(U45-Pad43)") (class "Default")
      (node (ref "U45") (pin "43") (pinfunction "43_43") (pintype "unspecified+no_connect"))
    )
    (net (code "136") (name "unconnected-(U45-Pad44)") (class "Default")
      (node (ref "U45") (pin "44") (pinfunction "44_44") (pintype "unspecified+no_connect"))
    )
    (net (code "137") (name "unconnected-(U45-Pad45)") (class "Default")
      (node (ref "U45") (pin "45") (pinfunction "45_45") (pintype "unspecified+no_connect"))
    )
    (net (code "138") (name "unconnected-(U45-Pad46)") (class "Default")
      (node (ref "U45") (pin "46") (pinfunction "46_46") (pintype "unspecified+no_connect"))
    )
    (net (code "139") (name "unconnected-(U45-Pad47)") (class "Default")
      (node (ref "U45") (pin "47") (pinfunction "47_47") (pintype "unspecified+no_connect"))
    )
    (net (code "140") (name "unconnected-(U45-Pad55)") (class "Default")
      (node (ref "U45") (pin "55") (pinfunction "55_55") (pintype "unspecified+no_connect"))
    )
    (net (code "141") (name "unconnected-(U45-Pad56)") (class "Default")
      (node (ref "U45") (pin "56") (pinfunction "56_56") (pintype "unspecified+no_connect"))
    )
    (net (code "142") (name "unconnected-(U45-Pad57)") (class "Default")
      (node (ref "U45") (pin "57") (pinfunction "57_57") (pintype "unspecified+no_connect"))
    )
    (net (code "143") (name "unconnected-(U45-Pad58)") (class "Default")
      (node (ref "U45") (pin "58") (pinfunction "58_58") (pintype "unspecified+no_connect"))
    )
    (net (code "144") (name "unconnected-(U45-Pad59)") (class "Default")
      (node (ref "U45") (pin "59") (pinfunction "59_59") (pintype "unspecified+no_connect"))
    )
    (net (code "145") (name "unconnected-(U45-Pad60)") (class "Default")
      (node (ref "U45") (pin "60") (pinfunction "60_60") (pintype "unspecified+no_connect"))
    )
    (net (code "146") (name "unconnected-(U45-Pad61)") (class "Default")
      (node (ref "U45") (pin "61") (pinfunction "61_61") (pintype "unspecified+no_connect"))
    )
    (net (code "147") (name "unconnected-(U45-Pad62)") (class "Default")
      (node (ref "U45") (pin "62") (pinfunction "62_62") (pintype "unspecified+no_connect"))
    )
    (net (code "148") (name "unconnected-(U45-Pad63)") (class "Default")
      (node (ref "U45") (pin "63") (pinfunction "63_63") (pintype "unspecified+no_connect"))
    )
    (net (code "149") (name "unconnected-(U45-Pad64)") (class "Default")
      (node (ref "U45") (pin "64") (pinfunction "64_64") (pintype "unspecified+no_connect"))
    )
    (net (code "150") (name "unconnected-(U45-Pad65)") (class "Default")
      (node (ref "U45") (pin "65") (pinfunction "65_65") (pintype "unspecified+no_connect"))
    )
    (net (code "151") (name "unconnected-(U45-Pad66)") (class "Default")
      (node (ref "U45") (pin "66") (pinfunction "66_66") (pintype "unspecified+no_connect"))
    )
    (net (code "152") (name "unconnected-(U45-Pad67)") (class "Default")
      (node (ref "U45") (pin "67") (pinfunction "67_67") (pintype "unspecified+no_connect"))
    )
    (net (code "153") (name "unconnected-(U45-Pad68)") (class "Default")
      (node (ref "U45") (pin "68") (pinfunction "68_68") (pintype "unspecified+no_connect"))
    )
    (net (code "154") (name "unconnected-(U45-Pad69)") (class "Default")
      (node (ref "U45") (pin "69") (pinfunction "69_69") (pintype "unspecified+no_connect"))
    )
    (net (code "155") (name "unconnected-(U45-Pad70)") (class "Default")
      (node (ref "U45") (pin "70") (pinfunction "70_70") (pintype "unspecified+no_connect"))
    )
    (net (code "156") (name "unconnected-(U45-Pad71)") (class "Default")
      (node (ref "U45") (pin "71") (pinfunction "71_71") (pintype "unspecified+no_connect"))
    )
    (net (code "157") (name "unconnected-(U45-Pad97)") (class "Default")
      (node (ref "U45") (pin "97") (pinfunction "97_97") (pintype "unspecified+no_connect"))
    )
    (net (code "158") (name "unconnected-(U45-Pad98)") (class "Default")
      (node (ref "U45") (pin "98") (pinfunction "98_98") (pintype "unspecified+no_connect"))
    )
    (net (code "159") (name "unconnected-(U45-Pad99)") (class "Default")
      (node (ref "U45") (pin "99") (pinfunction "99_99") (pintype "unspecified+no_connect"))
    )
    (net (code "160") (name "unconnected-(U45-Pad100)") (class "Default")
      (node (ref "U45") (pin "100") (pinfunction "100_100") (pintype "unspecified+no_connect"))
    )
    (net (code "161") (name "unconnected-(U45-Pad101)") (class "Default")
      (node (ref "U45") (pin "101") (pinfunction "101_101") (pintype "unspecified+no_connect"))
    )
    (net (code "162") (name "unconnected-(U45-Pad102)") (class "Default")
      (node (ref "U45") (pin "102") (pinfunction "102_102") (pintype "unspecified+no_connect"))
    )
    (net (code "163") (name "unconnected-(U45-Pad107)") (class "Default")
      (node (ref "U45") (pin "107") (pinfunction "107_107") (pintype "unspecified+no_connect"))
    )
    (net (code "164") (name "unconnected-(U45-Pad108)") (class "Default")
      (node (ref "U45") (pin "108") (pinfunction "108_108") (pintype "unspecified+no_connect"))
    )
    (net (code "165") (name "unconnected-(U45-Pad109)") (class "Default")
      (node (ref "U45") (pin "109") (pinfunction "109_109") (pintype "unspecified+no_connect"))
    )
    (net (code "166") (name "unconnected-(U45-Pad110)") (class "Default")
      (node (ref "U45") (pin "110") (pinfunction "110_110") (pintype "unspecified+no_connect"))
    )
    (net (code "167") (name "unconnected-(U45-Pad111)") (class "Default")
      (node (ref "U45") (pin "111") (pinfunction "111_111") (pintype "unspecified+no_connect"))
    )
    (net (code "168") (name "unconnected-(U45-Pad112)") (class "Default")
      (node (ref "U45") (pin "112") (pinfunction "112_112") (pintype "unspecified+no_connect"))
    )
    (net (code "169") (name "unconnected-(U45-Pad113)") (class "Default")
      (node (ref "U45") (pin "113") (pinfunction "113_113") (pintype "unspecified+no_connect"))
    )
    (net (code "170") (name "unconnected-(U45-Pad114)") (class "Default")
      (node (ref "U45") (pin "114") (pinfunction "114_114") (pintype "unspecified+no_connect"))
    )
    (net (code "171") (name "unconnected-(U45-Pad115)") (class "Default")
      (node (ref "U45") (pin "115") (pinfunction "115_115") (pintype "unspecified+no_connect"))
    )
    (net (code "172") (name "unconnected-(U45-Pad116)") (class "Default")
      (node (ref "U45") (pin "116") (pinfunction "116_116") (pintype "unspecified+no_connect"))
    )
    (net (code "173") (name "unconnected-(U45-Pad117)") (class "Default")
      (node (ref "U45") (pin "117") (pinfunction "117_117") (pintype "unspecified+no_connect"))
    )
    (net (code "174") (name "unconnected-(U45-Pad119)") (class "Default")
      (node (ref "U45") (pin "119") (pinfunction "119_119") (pintype "unspecified+no_connect"))
    )
    (net (code "175") (name "unconnected-(U45-Pad120)") (class "Default")
      (node (ref "U45") (pin "120") (pinfunction "120_120") (pintype "unspecified+no_connect"))
    )
    (net (code "176") (name "unconnected-(U45-Pad124)") (class "Default")
      (node (ref "U45") (pin "124") (pinfunction "124_124") (pintype "unspecified+no_connect"))
    )
    (net (code "177") (name "unconnected-(U45-Pad125)") (class "Default")
      (node (ref "U45") (pin "125") (pinfunction "125_125") (pintype "unspecified+no_connect"))
    )
    (net (code "178") (name "unconnected-(U45-Pad126)") (class "Default")
      (node (ref "U45") (pin "126") (pinfunction "126_126") (pintype "unspecified+no_connect"))
    )
    (net (code "179") (name "unconnected-(U45-Pad128)") (class "Default")
      (node (ref "U45") (pin "128") (pinfunction "128_128") (pintype "unspecified+no_connect"))
    )
    (net (code "180") (name "unconnected-(U45-Pad129)") (class "Default")
      (node (ref "U45") (pin "129") (pinfunction "129_129") (pintype "unspecified+no_connect"))
    )
    (net (code "181") (name "unconnected-(U45-Pad130)") (class "Default")
      (node (ref "U45") (pin "130") (pinfunction "130_130") (pintype "unspecified+no_connect"))
    )
    (net (code "182") (name "unconnected-(U45-Pad131)") (class "Default")
      (node (ref "U45") (pin "131") (pinfunction "131_131") (pintype "unspecified+no_connect"))
    )
    (net (code "183") (name "unconnected-(U45-Pad132)") (class "Default")
      (node (ref "U45") (pin "132") (pinfunction "132_132") (pintype "unspecified+no_connect"))
    )
    (net (code "184") (name "unconnected-(U45-Pad133)") (class "Default")
      (node (ref "U45") (pin "133") (pinfunction "133_133") (pintype "unspecified+no_connect"))
    )
    (net (code "185") (name "unconnected-(U45-Pad134)") (class "Default")
      (node (ref "U45") (pin "134") (pinfunction "134_134") (pintype "unspecified+no_connect"))
    )
    (net (code "186") (name "unconnected-(U45-Pad135)") (class "Default")
      (node (ref "U45") (pin "135") (pinfunction "135_135") (pintype "unspecified+no_connect"))
    )
    (net (code "187") (name "unconnected-(U45-Pad136)") (class "Default")
      (node (ref "U45") (pin "136") (pinfunction "136_136") (pintype "unspecified+no_connect"))
    )
    (net (code "188") (name "unconnected-(U45-Pad137)") (class "Default")
      (node (ref "U45") (pin "137") (pinfunction "137_137") (pintype "unspecified+no_connect"))
    )
    (net (code "189") (name "unconnected-(U45-Pad138)") (class "Default")
      (node (ref "U45") (pin "138") (pinfunction "138_138") (pintype "unspecified+no_connect"))
    )
    (net (code "190") (name "unconnected-(U45-Pad139)") (class "Default")
      (node (ref "U45") (pin "139") (pinfunction "139_139") (pintype "unspecified+no_connect"))
    )
    (net (code "191") (name "unconnected-(U45-Pad140)") (class "Default")
      (node (ref "U45") (pin "140") (pinfunction "140_140") (pintype "unspecified+no_connect"))
    )
    (net (code "192") (name "unconnected-(USBC6-SBU1-PadA8)") (class "Default")
      (node (ref "USBC6") (pin "A8") (pinfunction "SBU1_A8") (pintype "unspecified+no_connect"))
    )
    (net (code "193") (name "unconnected-(USBC6-SBU2-PadB8)") (class "Default")
      (node (ref "USBC6") (pin "B8") (pinfunction "SBU2_B8") (pintype "unspecified+no_connect"))
    )
    (net (code "194") (name "unconnected-(USBC8-SBU1-PadA8)") (class "Default")
      (node (ref "USBC8") (pin "A8") (pinfunction "SBU1_A8") (pintype "unspecified+no_connect"))
    )
    (net (code "195") (name "unconnected-(USBC8-SBU2-PadB8)") (class "Default")
      (node (ref "USBC8") (pin "B8") (pinfunction "SBU2_B8") (pintype "unspecified+no_connect"))
    )
  )
)
